# PCB-Relay-Board-V1.net
KiCad netlist of a schematic drawn in Altium Designer
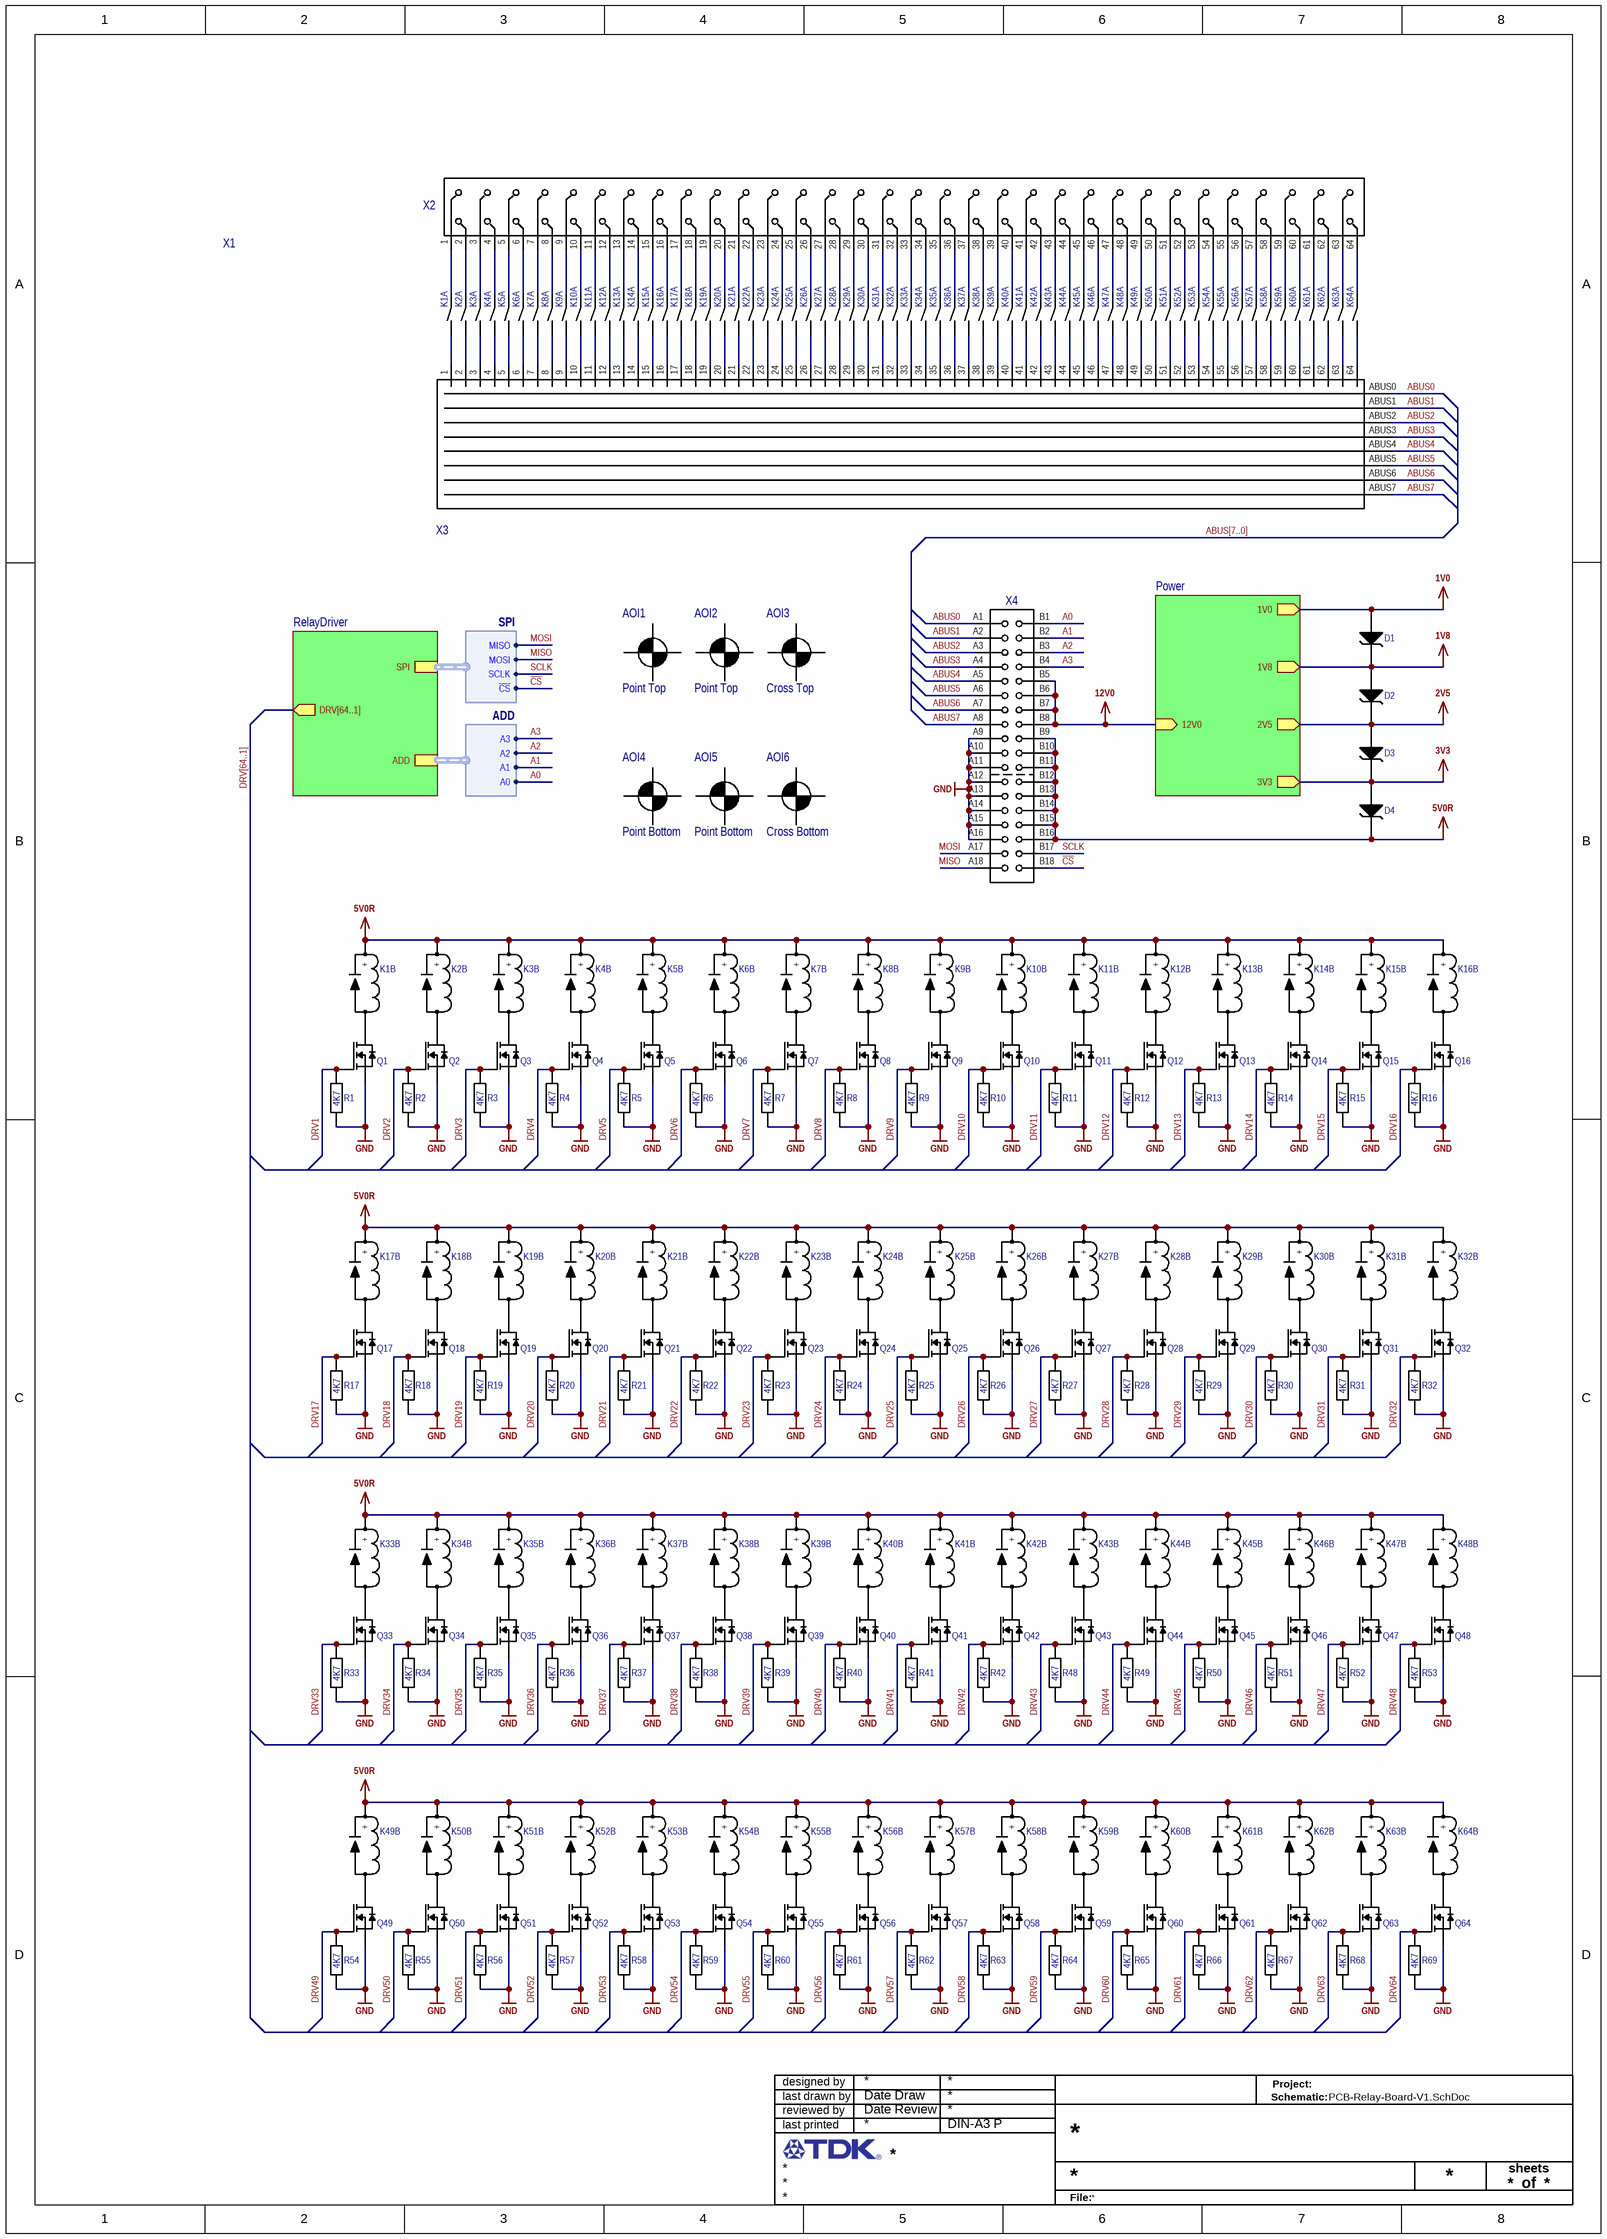
[diagram p0: PCB-Relay-Board-V1.SchDoc]

(export (version "E")
  (design (tool "Eeschema 10.0.6"))
  (components
    (comp (ref "AOI1")
      (value "AOI")
      (footprint "Fiducial Point")
      (description "Assembly AOI")
      (fields (field (name "SHAPE") "Point Top") (field (name "13. CREATED DATE/NAME") "AUG2018/Hören"))
      (libsource (lib "chickenfood") (part "Fiducial"))
    )
    (comp (ref "AOI2")
      (value "AOI")
      (footprint "Fiducial Point")
      (description "Assembly AOI")
      (fields (field (name "SHAPE") "Point Top") (field (name "13. CREATED DATE/NAME") "AUG2018/Hören"))
      (libsource (lib "chickenfood") (part "Fiducial"))
    )
    (comp (ref "AOI3")
      (value "AOI")
      (footprint "Fiducial Cross")
      (description "Assembly AOI")
      (fields (field (name "SHAPE") "Cross Top") (field (name "13. CREATED DATE/NAME") "AUG2018/Hören"))
      (libsource (lib "chickenfood") (part "Fiducial"))
    )
    (comp (ref "AOI4")
      (value "AOI")
      (footprint "Fiducial Point")
      (description "Assembly AOI")
      (fields (field (name "SHAPE") "Point Bottom") (field (name "13. CREATED DATE/NAME") "AUG2018/Hören"))
      (libsource (lib "chickenfood") (part "Fiducial"))
    )
    (comp (ref "AOI5")
      (value "AOI")
      (footprint "Fiducial Point")
      (description "Assembly AOI")
      (fields (field (name "SHAPE") "Point Bottom") (field (name "13. CREATED DATE/NAME") "AUG2018/Hören"))
      (libsource (lib "chickenfood") (part "Fiducial"))
    )
    (comp (ref "AOI6")
      (value "AOI")
      (footprint "Fiducial Cross")
      (description "Assembly AOI")
      (fields (field (name "SHAPE") "Cross Bottom") (field (name "13. CREATED DATE/NAME") "AUG2018/Hören"))
      (libsource (lib "chickenfood") (part "Fiducial"))
    )
    (comp (ref "D1")
      (value "D")
      (footprint "SOD128")
      (description "DIODE SCHOTTKY 40V 5A SOD128")
      (fields
        (field (name "02. DISTRIBUTOR PART NUMBER") "1727-5842-6-ND")
        (field (name "07. MANUFACTURER  PART NUMBER") "PMEG4050EP,115")
        (field (name "13. CREATED DATE/NAME") "AUG2018/Hören")
      )
      (libsource (lib "chickenfood") (part "Dz"))
    )
    (comp (ref "D2")
      (value "D")
      (footprint "SOD128")
      (description "DIODE SCHOTTKY 40V 5A SOD128")
      (fields
        (field (name "02. DISTRIBUTOR PART NUMBER") "1727-5842-6-ND")
        (field (name "07. MANUFACTURER  PART NUMBER") "PMEG4050EP,115")
        (field (name "13. CREATED DATE/NAME") "AUG2018/Hören")
      )
      (libsource (lib "chickenfood") (part "Dz"))
    )
    (comp (ref "D3")
      (value "D")
      (footprint "SOD128")
      (description "DIODE SCHOTTKY 40V 5A SOD128")
      (fields
        (field (name "02. DISTRIBUTOR PART NUMBER") "1727-5842-6-ND")
        (field (name "07. MANUFACTURER  PART NUMBER") "PMEG4050EP,115")
        (field (name "13. CREATED DATE/NAME") "AUG2018/Hören")
      )
      (libsource (lib "chickenfood") (part "Dz"))
    )
    (comp (ref "D4")
      (value "D")
      (footprint "SOD128")
      (description "DIODE SCHOTTKY 40V 5A SOD128")
      (fields
        (field (name "02. DISTRIBUTOR PART NUMBER") "1727-5842-6-ND")
        (field (name "07. MANUFACTURER  PART NUMBER") "PMEG4050EP,115")
        (field (name "13. CREATED DATE/NAME") "AUG2018/Hören")
      )
      (libsource (lib "chickenfood") (part "Dz"))
    )
    (comp (ref "K1")
      (value "K")
      (footprint "118-1A")
      (description "5V Signal Relais, Normal Open")
      (fields
        (field (name "02. DISTRIBUTOR PART NUMBER") "118-1-A-5/2D")
        (field (name "13. CREATED DATE/NAME") "20.12.17 S. Kaiser")
      )
      (libsource (lib "chickenfood") (part "118-1-A-5/2D"))
    )
    (comp (ref "K2")
      (value "K")
      (footprint "118-1A")
      (description "5V Signal Relais, Normal Open")
      (fields
        (field (name "02. DISTRIBUTOR PART NUMBER") "118-1-A-5/2D")
        (field (name "13. CREATED DATE/NAME") "20.12.17 S. Kaiser")
      )
      (libsource (lib "") (part "118-1-A-5/2D_1"))
    )
    (comp (ref "K3")
      (value "K")
      (footprint "118-1A")
      (description "5V Signal Relais, Normal Open")
      (fields
        (field (name "02. DISTRIBUTOR PART NUMBER") "118-1-A-5/2D")
        (field (name "13. CREATED DATE/NAME") "20.12.17 S. Kaiser")
      )
      (libsource (lib "chickenfood") (part "118-1-A-5/2D"))
    )
    (comp (ref "K4")
      (value "K")
      (footprint "118-1A")
      (description "5V Signal Relais, Normal Open")
      (fields
        (field (name "02. DISTRIBUTOR PART NUMBER") "118-1-A-5/2D")
        (field (name "13. CREATED DATE/NAME") "20.12.17 S. Kaiser")
      )
      (libsource (lib "chickenfood") (part "118-1-A-5/2D"))
    )
    (comp (ref "K5")
      (value "K")
      (footprint "118-1A")
      (description "5V Signal Relais, Normal Open")
      (fields
        (field (name "02. DISTRIBUTOR PART NUMBER") "118-1-A-5/2D")
        (field (name "13. CREATED DATE/NAME") "20.12.17 S. Kaiser")
      )
      (libsource (lib "") (part "118-1-A-5/2D_1"))
    )
    (comp (ref "K6")
      (value "K")
      (footprint "118-1A")
      (description "5V Signal Relais, Normal Open")
      (fields
        (field (name "02. DISTRIBUTOR PART NUMBER") "118-1-A-5/2D")
        (field (name "13. CREATED DATE/NAME") "20.12.17 S. Kaiser")
      )
      (libsource (lib "") (part "118-1-A-5/2D_1"))
    )
    (comp (ref "K7")
      (value "K")
      (footprint "118-1A")
      (description "5V Signal Relais, Normal Open")
      (fields
        (field (name "02. DISTRIBUTOR PART NUMBER") "118-1-A-5/2D")
        (field (name "13. CREATED DATE/NAME") "20.12.17 S. Kaiser")
      )
      (libsource (lib "chickenfood") (part "118-1-A-5/2D"))
    )
    (comp (ref "K8")
      (value "K")
      (footprint "118-1A")
      (description "5V Signal Relais, Normal Open")
      (fields
        (field (name "02. DISTRIBUTOR PART NUMBER") "118-1-A-5/2D")
        (field (name "13. CREATED DATE/NAME") "20.12.17 S. Kaiser")
      )
      (libsource (lib "chickenfood") (part "118-1-A-5/2D"))
    )
    (comp (ref "K9")
      (value "K")
      (footprint "118-1A")
      (description "5V Signal Relais, Normal Open")
      (fields
        (field (name "02. DISTRIBUTOR PART NUMBER") "118-1-A-5/2D")
        (field (name "13. CREATED DATE/NAME") "20.12.17 S. Kaiser")
      )
      (libsource (lib "") (part "118-1-A-5/2D_1"))
    )
    (comp (ref "K10")
      (value "K")
      (footprint "118-1A")
      (description "5V Signal Relais, Normal Open")
      (fields
        (field (name "02. DISTRIBUTOR PART NUMBER") "118-1-A-5/2D")
        (field (name "13. CREATED DATE/NAME") "20.12.17 S. Kaiser")
      )
      (libsource (lib "") (part "118-1-A-5/2D_1"))
    )
    (comp (ref "K11")
      (value "K")
      (footprint "118-1A")
      (description "5V Signal Relais, Normal Open")
      (fields
        (field (name "02. DISTRIBUTOR PART NUMBER") "118-1-A-5/2D")
        (field (name "13. CREATED DATE/NAME") "20.12.17 S. Kaiser")
      )
      (libsource (lib "") (part "118-1-A-5/2D_1"))
    )
    (comp (ref "K12")
      (value "K")
      (footprint "118-1A")
      (description "5V Signal Relais, Normal Open")
      (fields
        (field (name "02. DISTRIBUTOR PART NUMBER") "118-1-A-5/2D")
        (field (name "13. CREATED DATE/NAME") "20.12.17 S. Kaiser")
      )
      (libsource (lib "chickenfood") (part "118-1-A-5/2D"))
    )
    (comp (ref "K13")
      (value "K")
      (footprint "118-1A")
      (description "5V Signal Relais, Normal Open")
      (fields
        (field (name "02. DISTRIBUTOR PART NUMBER") "118-1-A-5/2D")
        (field (name "13. CREATED DATE/NAME") "20.12.17 S. Kaiser")
      )
      (libsource (lib "") (part "118-1-A-5/2D_1"))
    )
    (comp (ref "K14")
      (value "K")
      (footprint "118-1A")
      (description "5V Signal Relais, Normal Open")
      (fields
        (field (name "02. DISTRIBUTOR PART NUMBER") "118-1-A-5/2D")
        (field (name "13. CREATED DATE/NAME") "20.12.17 S. Kaiser")
      )
      (libsource (lib "chickenfood") (part "118-1-A-5/2D"))
    )
    (comp (ref "K15")
      (value "K")
      (footprint "118-1A")
      (description "5V Signal Relais, Normal Open")
      (fields
        (field (name "02. DISTRIBUTOR PART NUMBER") "118-1-A-5/2D")
        (field (name "13. CREATED DATE/NAME") "20.12.17 S. Kaiser")
      )
      (libsource (lib "chickenfood") (part "118-1-A-5/2D"))
    )
    (comp (ref "K16")
      (value "K")
      (footprint "118-1A")
      (description "5V Signal Relais, Normal Open")
      (fields
        (field (name "02. DISTRIBUTOR PART NUMBER") "118-1-A-5/2D")
        (field (name "13. CREATED DATE/NAME") "20.12.17 S. Kaiser")
      )
      (libsource (lib "chickenfood") (part "118-1-A-5/2D"))
    )
    (comp (ref "K17")
      (value "K")
      (footprint "118-1A")
      (description "5V Signal Relais, Normal Open")
      (fields
        (field (name "02. DISTRIBUTOR PART NUMBER") "118-1-A-5/2D")
        (field (name "13. CREATED DATE/NAME") "20.12.17 S. Kaiser")
      )
      (libsource (lib "") (part "118-1-A-5/2D_1"))
    )
    (comp (ref "K18")
      (value "K")
      (footprint "118-1A")
      (description "5V Signal Relais, Normal Open")
      (fields
        (field (name "02. DISTRIBUTOR PART NUMBER") "118-1-A-5/2D")
        (field (name "13. CREATED DATE/NAME") "20.12.17 S. Kaiser")
      )
      (libsource (lib "chickenfood") (part "118-1-A-5/2D"))
    )
    (comp (ref "K19")
      (value "K")
      (footprint "118-1A")
      (description "5V Signal Relais, Normal Open")
      (fields
        (field (name "02. DISTRIBUTOR PART NUMBER") "118-1-A-5/2D")
        (field (name "13. CREATED DATE/NAME") "20.12.17 S. Kaiser")
      )
      (libsource (lib "chickenfood") (part "118-1-A-5/2D"))
    )
    (comp (ref "K20")
      (value "K")
      (footprint "118-1A")
      (description "5V Signal Relais, Normal Open")
      (fields
        (field (name "02. DISTRIBUTOR PART NUMBER") "118-1-A-5/2D")
        (field (name "13. CREATED DATE/NAME") "20.12.17 S. Kaiser")
      )
      (libsource (lib "chickenfood") (part "118-1-A-5/2D"))
    )
    (comp (ref "K21")
      (value "K")
      (footprint "118-1A")
      (description "5V Signal Relais, Normal Open")
      (fields
        (field (name "02. DISTRIBUTOR PART NUMBER") "118-1-A-5/2D")
        (field (name "13. CREATED DATE/NAME") "20.12.17 S. Kaiser")
      )
      (libsource (lib "") (part "118-1-A-5/2D_1"))
    )
    (comp (ref "K22")
      (value "K")
      (footprint "118-1A")
      (description "5V Signal Relais, Normal Open")
      (fields
        (field (name "02. DISTRIBUTOR PART NUMBER") "118-1-A-5/2D")
        (field (name "13. CREATED DATE/NAME") "20.12.17 S. Kaiser")
      )
      (libsource (lib "chickenfood") (part "118-1-A-5/2D"))
    )
    (comp (ref "K23")
      (value "K")
      (footprint "118-1A")
      (description "5V Signal Relais, Normal Open")
      (fields
        (field (name "02. DISTRIBUTOR PART NUMBER") "118-1-A-5/2D")
        (field (name "13. CREATED DATE/NAME") "20.12.17 S. Kaiser")
      )
      (libsource (lib "chickenfood") (part "118-1-A-5/2D"))
    )
    (comp (ref "K24")
      (value "K")
      (footprint "118-1A")
      (description "5V Signal Relais, Normal Open")
      (fields
        (field (name "02. DISTRIBUTOR PART NUMBER") "118-1-A-5/2D")
        (field (name "13. CREATED DATE/NAME") "20.12.17 S. Kaiser")
      )
      (libsource (lib "") (part "118-1-A-5/2D_1"))
    )
    (comp (ref "K25")
      (value "K")
      (footprint "118-1A")
      (description "5V Signal Relais, Normal Open")
      (fields
        (field (name "02. DISTRIBUTOR PART NUMBER") "118-1-A-5/2D")
        (field (name "13. CREATED DATE/NAME") "20.12.17 S. Kaiser")
      )
      (libsource (lib "") (part "118-1-A-5/2D_1"))
    )
    (comp (ref "K26")
      (value "K")
      (footprint "118-1A")
      (description "5V Signal Relais, Normal Open")
      (fields
        (field (name "02. DISTRIBUTOR PART NUMBER") "118-1-A-5/2D")
        (field (name "13. CREATED DATE/NAME") "20.12.17 S. Kaiser")
      )
      (libsource (lib "chickenfood") (part "118-1-A-5/2D"))
    )
    (comp (ref "K27")
      (value "K")
      (footprint "118-1A")
      (description "5V Signal Relais, Normal Open")
      (fields
        (field (name "02. DISTRIBUTOR PART NUMBER") "118-1-A-5/2D")
        (field (name "13. CREATED DATE/NAME") "20.12.17 S. Kaiser")
      )
      (libsource (lib "chickenfood") (part "118-1-A-5/2D"))
    )
    (comp (ref "K28")
      (value "K")
      (footprint "118-1A")
      (description "5V Signal Relais, Normal Open")
      (fields
        (field (name "02. DISTRIBUTOR PART NUMBER") "118-1-A-5/2D")
        (field (name "13. CREATED DATE/NAME") "20.12.17 S. Kaiser")
      )
      (libsource (lib "") (part "118-1-A-5/2D_1"))
    )
    (comp (ref "K29")
      (value "K")
      (footprint "118-1A")
      (description "5V Signal Relais, Normal Open")
      (fields
        (field (name "02. DISTRIBUTOR PART NUMBER") "118-1-A-5/2D")
        (field (name "13. CREATED DATE/NAME") "20.12.17 S. Kaiser")
      )
      (libsource (lib "chickenfood") (part "118-1-A-5/2D"))
    )
    (comp (ref "K30")
      (value "K")
      (footprint "118-1A")
      (description "5V Signal Relais, Normal Open")
      (fields
        (field (name "02. DISTRIBUTOR PART NUMBER") "118-1-A-5/2D")
        (field (name "13. CREATED DATE/NAME") "20.12.17 S. Kaiser")
      )
      (libsource (lib "") (part "118-1-A-5/2D_1"))
    )
    (comp (ref "K31")
      (value "K")
      (footprint "118-1A")
      (description "5V Signal Relais, Normal Open")
      (fields
        (field (name "02. DISTRIBUTOR PART NUMBER") "118-1-A-5/2D")
        (field (name "13. CREATED DATE/NAME") "20.12.17 S. Kaiser")
      )
      (libsource (lib "") (part "118-1-A-5/2D_1"))
    )
    (comp (ref "K32")
      (value "K")
      (footprint "118-1A")
      (description "5V Signal Relais, Normal Open")
      (fields
        (field (name "02. DISTRIBUTOR PART NUMBER") "118-1-A-5/2D")
        (field (name "13. CREATED DATE/NAME") "20.12.17 S. Kaiser")
      )
      (libsource (lib "chickenfood") (part "118-1-A-5/2D"))
    )
    (comp (ref "K33")
      (value "K")
      (footprint "118-1A")
      (description "5V Signal Relais, Normal Open")
      (fields
        (field (name "02. DISTRIBUTOR PART NUMBER") "118-1-A-5/2D")
        (field (name "13. CREATED DATE/NAME") "20.12.17 S. Kaiser")
      )
      (libsource (lib "") (part "118-1-A-5/2D_1"))
    )
    (comp (ref "K34")
      (value "K")
      (footprint "118-1A")
      (description "5V Signal Relais, Normal Open")
      (fields
        (field (name "02. DISTRIBUTOR PART NUMBER") "118-1-A-5/2D")
        (field (name "13. CREATED DATE/NAME") "20.12.17 S. Kaiser")
      )
      (libsource (lib "") (part "118-1-A-5/2D_1"))
    )
    (comp (ref "K35")
      (value "K")
      (footprint "118-1A")
      (description "5V Signal Relais, Normal Open")
      (fields
        (field (name "02. DISTRIBUTOR PART NUMBER") "118-1-A-5/2D")
        (field (name "13. CREATED DATE/NAME") "20.12.17 S. Kaiser")
      )
      (libsource (lib "chickenfood") (part "118-1-A-5/2D"))
    )
    (comp (ref "K36")
      (value "K")
      (footprint "118-1A")
      (description "5V Signal Relais, Normal Open")
      (fields
        (field (name "02. DISTRIBUTOR PART NUMBER") "118-1-A-5/2D")
        (field (name "13. CREATED DATE/NAME") "20.12.17 S. Kaiser")
      )
      (libsource (lib "chickenfood") (part "118-1-A-5/2D"))
    )
    (comp (ref "K37")
      (value "K")
      (footprint "118-1A")
      (description "5V Signal Relais, Normal Open")
      (fields
        (field (name "02. DISTRIBUTOR PART NUMBER") "118-1-A-5/2D")
        (field (name "13. CREATED DATE/NAME") "20.12.17 S. Kaiser")
      )
      (libsource (lib "chickenfood") (part "118-1-A-5/2D"))
    )
    (comp (ref "K38")
      (value "K")
      (footprint "118-1A")
      (description "5V Signal Relais, Normal Open")
      (fields
        (field (name "02. DISTRIBUTOR PART NUMBER") "118-1-A-5/2D")
        (field (name "13. CREATED DATE/NAME") "20.12.17 S. Kaiser")
      )
      (libsource (lib "") (part "118-1-A-5/2D_1"))
    )
    (comp (ref "K39")
      (value "K")
      (footprint "118-1A")
      (description "5V Signal Relais, Normal Open")
      (fields
        (field (name "02. DISTRIBUTOR PART NUMBER") "118-1-A-5/2D")
        (field (name "13. CREATED DATE/NAME") "20.12.17 S. Kaiser")
      )
      (libsource (lib "chickenfood") (part "118-1-A-5/2D"))
    )
    (comp (ref "K40")
      (value "K")
      (footprint "118-1A")
      (description "5V Signal Relais, Normal Open")
      (fields
        (field (name "02. DISTRIBUTOR PART NUMBER") "118-1-A-5/2D")
        (field (name "13. CREATED DATE/NAME") "20.12.17 S. Kaiser")
      )
      (libsource (lib "chickenfood") (part "118-1-A-5/2D"))
    )
    (comp (ref "K41")
      (value "K")
      (footprint "118-1A")
      (description "5V Signal Relais, Normal Open")
      (fields
        (field (name "02. DISTRIBUTOR PART NUMBER") "118-1-A-5/2D")
        (field (name "13. CREATED DATE/NAME") "20.12.17 S. Kaiser")
      )
      (libsource (lib "chickenfood") (part "118-1-A-5/2D"))
    )
    (comp (ref "K42")
      (value "K")
      (footprint "118-1A")
      (description "5V Signal Relais, Normal Open")
      (fields
        (field (name "02. DISTRIBUTOR PART NUMBER") "118-1-A-5/2D")
        (field (name "13. CREATED DATE/NAME") "20.12.17 S. Kaiser")
      )
      (libsource (lib "") (part "118-1-A-5/2D_1"))
    )
    (comp (ref "K43")
      (value "K")
      (footprint "118-1A")
      (description "5V Signal Relais, Normal Open")
      (fields
        (field (name "02. DISTRIBUTOR PART NUMBER") "118-1-A-5/2D")
        (field (name "13. CREATED DATE/NAME") "20.12.17 S. Kaiser")
      )
      (libsource (lib "chickenfood") (part "118-1-A-5/2D"))
    )
    (comp (ref "K44")
      (value "K")
      (footprint "118-1A")
      (description "5V Signal Relais, Normal Open")
      (fields
        (field (name "02. DISTRIBUTOR PART NUMBER") "118-1-A-5/2D")
        (field (name "13. CREATED DATE/NAME") "20.12.17 S. Kaiser")
      )
      (libsource (lib "") (part "118-1-A-5/2D_1"))
    )
    (comp (ref "K45")
      (value "K")
      (footprint "118-1A")
      (description "5V Signal Relais, Normal Open")
      (fields
        (field (name "02. DISTRIBUTOR PART NUMBER") "118-1-A-5/2D")
        (field (name "13. CREATED DATE/NAME") "20.12.17 S. Kaiser")
      )
      (libsource (lib "chickenfood") (part "118-1-A-5/2D"))
    )
    (comp (ref "K46")
      (value "K")
      (footprint "118-1A")
      (description "5V Signal Relais, Normal Open")
      (fields
        (field (name "02. DISTRIBUTOR PART NUMBER") "118-1-A-5/2D")
        (field (name "13. CREATED DATE/NAME") "20.12.17 S. Kaiser")
      )
      (libsource (lib "") (part "118-1-A-5/2D_1"))
    )
    (comp (ref "K47")
      (value "K")
      (footprint "118-1A")
      (description "5V Signal Relais, Normal Open")
      (fields
        (field (name "02. DISTRIBUTOR PART NUMBER") "118-1-A-5/2D")
        (field (name "13. CREATED DATE/NAME") "20.12.17 S. Kaiser")
      )
      (libsource (lib "chickenfood") (part "118-1-A-5/2D"))
    )
    (comp (ref "K48")
      (value "K")
      (footprint "118-1A")
      (description "5V Signal Relais, Normal Open")
      (fields
        (field (name "02. DISTRIBUTOR PART NUMBER") "118-1-A-5/2D")
        (field (name "13. CREATED DATE/NAME") "20.12.17 S. Kaiser")
      )
      (libsource (lib "chickenfood") (part "118-1-A-5/2D"))
    )
    (comp (ref "K49")
      (value "K")
      (footprint "118-1A")
      (description "5V Signal Relais, Normal Open")
      (fields
        (field (name "02. DISTRIBUTOR PART NUMBER") "118-1-A-5/2D")
        (field (name "13. CREATED DATE/NAME") "20.12.17 S. Kaiser")
      )
      (libsource (lib "") (part "118-1-A-5/2D_1"))
    )
    (comp (ref "K50")
      (value "K")
      (footprint "118-1A")
      (description "5V Signal Relais, Normal Open")
      (fields
        (field (name "02. DISTRIBUTOR PART NUMBER") "118-1-A-5/2D")
        (field (name "13. CREATED DATE/NAME") "20.12.17 S. Kaiser")
      )
      (libsource (lib "chickenfood") (part "118-1-A-5/2D"))
    )
    (comp (ref "K51")
      (value "K")
      (footprint "118-1A")
      (description "5V Signal Relais, Normal Open")
      (fields
        (field (name "02. DISTRIBUTOR PART NUMBER") "118-1-A-5/2D")
        (field (name "13. CREATED DATE/NAME") "20.12.17 S. Kaiser")
      )
      (libsource (lib "") (part "118-1-A-5/2D_1"))
    )
    (comp (ref "K52")
      (value "K")
      (footprint "118-1A")
      (description "5V Signal Relais, Normal Open")
      (fields
        (field (name "02. DISTRIBUTOR PART NUMBER") "118-1-A-5/2D")
        (field (name "13. CREATED DATE/NAME") "20.12.17 S. Kaiser")
      )
      (libsource (lib "chickenfood") (part "118-1-A-5/2D"))
    )
    (comp (ref "K53")
      (value "K")
      (footprint "118-1A")
      (description "5V Signal Relais, Normal Open")
      (fields
        (field (name "02. DISTRIBUTOR PART NUMBER") "118-1-A-5/2D")
        (field (name "13. CREATED DATE/NAME") "20.12.17 S. Kaiser")
      )
      (libsource (lib "chickenfood") (part "118-1-A-5/2D"))
    )
    (comp (ref "K54")
      (value "K")
      (footprint "118-1A")
      (description "5V Signal Relais, Normal Open")
      (fields
        (field (name "02. DISTRIBUTOR PART NUMBER") "118-1-A-5/2D")
        (field (name "13. CREATED DATE/NAME") "20.12.17 S. Kaiser")
      )
      (libsource (lib "chickenfood") (part "118-1-A-5/2D"))
    )
    (comp (ref "K55")
      (value "K")
      (footprint "118-1A")
      (description "5V Signal Relais, Normal Open")
      (fields
        (field (name "02. DISTRIBUTOR PART NUMBER") "118-1-A-5/2D")
        (field (name "13. CREATED DATE/NAME") "20.12.17 S. Kaiser")
      )
      (libsource (lib "") (part "118-1-A-5/2D_1"))
    )
    (comp (ref "K56")
      (value "K")
      (footprint "118-1A")
      (description "5V Signal Relais, Normal Open")
      (fields
        (field (name "02. DISTRIBUTOR PART NUMBER") "118-1-A-5/2D")
        (field (name "13. CREATED DATE/NAME") "20.12.17 S. Kaiser")
      )
      (libsource (lib "") (part "118-1-A-5/2D_1"))
    )
    (comp (ref "K57")
      (value "K")
      (footprint "118-1A")
      (description "5V Signal Relais, Normal Open")
      (fields
        (field (name "02. DISTRIBUTOR PART NUMBER") "118-1-A-5/2D")
        (field (name "13. CREATED DATE/NAME") "20.12.17 S. Kaiser")
      )
      (libsource (lib "chickenfood") (part "118-1-A-5/2D"))
    )
    (comp (ref "K58")
      (value "K")
      (footprint "118-1A")
      (description "5V Signal Relais, Normal Open")
      (fields
        (field (name "02. DISTRIBUTOR PART NUMBER") "118-1-A-5/2D")
        (field (name "13. CREATED DATE/NAME") "20.12.17 S. Kaiser")
      )
      (libsource (lib "") (part "118-1-A-5/2D_1"))
    )
    (comp (ref "K59")
      (value "K")
      (footprint "118-1A")
      (description "5V Signal Relais, Normal Open")
      (fields
        (field (name "02. DISTRIBUTOR PART NUMBER") "118-1-A-5/2D")
        (field (name "13. CREATED DATE/NAME") "20.12.17 S. Kaiser")
      )
      (libsource (lib "chickenfood") (part "118-1-A-5/2D"))
    )
    (comp (ref "K60")
      (value "K")
      (footprint "118-1A")
      (description "5V Signal Relais, Normal Open")
      (fields
        (field (name "02. DISTRIBUTOR PART NUMBER") "118-1-A-5/2D")
        (field (name "13. CREATED DATE/NAME") "20.12.17 S. Kaiser")
      )
      (libsource (lib "") (part "118-1-A-5/2D_1"))
    )
    (comp (ref "K61")
      (value "K")
      (footprint "118-1A")
      (description "5V Signal Relais, Normal Open")
      (fields
        (field (name "02. DISTRIBUTOR PART NUMBER") "118-1-A-5/2D")
        (field (name "13. CREATED DATE/NAME") "20.12.17 S. Kaiser")
      )
      (libsource (lib "") (part "118-1-A-5/2D_1"))
    )
    (comp (ref "K62")
      (value "K")
      (footprint "118-1A")
      (description "5V Signal Relais, Normal Open")
      (fields
        (field (name "02. DISTRIBUTOR PART NUMBER") "118-1-A-5/2D")
        (field (name "13. CREATED DATE/NAME") "20.12.17 S. Kaiser")
      )
      (libsource (lib "chickenfood") (part "118-1-A-5/2D"))
    )
    (comp (ref "K63")
      (value "K")
      (footprint "118-1A")
      (description "5V Signal Relais, Normal Open")
      (fields
        (field (name "02. DISTRIBUTOR PART NUMBER") "118-1-A-5/2D")
        (field (name "13. CREATED DATE/NAME") "20.12.17 S. Kaiser")
      )
      (libsource (lib "") (part "118-1-A-5/2D_1"))
    )
    (comp (ref "K64")
      (value "K")
      (footprint "118-1A")
      (description "5V Signal Relais, Normal Open")
      (fields
        (field (name "02. DISTRIBUTOR PART NUMBER") "118-1-A-5/2D")
        (field (name "13. CREATED DATE/NAME") "20.12.17 S. Kaiser")
      )
      (libsource (lib "") (part "118-1-A-5/2D_1"))
    )
    (comp (ref "Q1")
      (value "Q")
      (footprint "SOT23-3")
      (description "MOSFET N-CH 25V 680MA SOT-23")
      (fields
        (field (name "02. DISTRIBUTOR PART NUMBER") "FDV303NDKR-ND")
        (field (name "07. MANUFACTURER  PART NUMBER") "FDV303N")
        (field (name "13. CREATED DATE/NAME") "AUG 2018 / Hören")
      )
      (libsource (lib "SCT8-Board1") (part "FDV303N"))
    )
    (comp (ref "Q2")
      (value "Q")
      (footprint "SOT23-3")
      (description "MOSFET N-CH 25V 680MA SOT-23")
      (fields
        (field (name "02. DISTRIBUTOR PART NUMBER") "FDV303NDKR-ND")
        (field (name "07. MANUFACTURER  PART NUMBER") "FDV303N")
        (field (name "13. CREATED DATE/NAME") "AUG 2018 / Hören")
      )
      (libsource (lib "SCT8-Board1") (part "FDV303N"))
    )
    (comp (ref "Q3")
      (value "Q")
      (footprint "SOT23-3")
      (description "MOSFET N-CH 25V 680MA SOT-23")
      (fields
        (field (name "02. DISTRIBUTOR PART NUMBER") "FDV303NDKR-ND")
        (field (name "07. MANUFACTURER  PART NUMBER") "FDV303N")
        (field (name "13. CREATED DATE/NAME") "AUG 2018 / Hören")
      )
      (libsource (lib "SCT8-Board1") (part "FDV303N"))
    )
    (comp (ref "Q4")
      (value "Q")
      (footprint "SOT23-3")
      (description "MOSFET N-CH 25V 680MA SOT-23")
      (fields
        (field (name "02. DISTRIBUTOR PART NUMBER") "FDV303NDKR-ND")
        (field (name "07. MANUFACTURER  PART NUMBER") "FDV303N")
        (field (name "13. CREATED DATE/NAME") "AUG 2018 / Hören")
      )
      (libsource (lib "SCT8-Board1") (part "FDV303N"))
    )
    (comp (ref "Q5")
      (value "Q")
      (footprint "SOT23-3")
      (description "MOSFET N-CH 25V 680MA SOT-23")
      (fields
        (field (name "02. DISTRIBUTOR PART NUMBER") "FDV303NDKR-ND")
        (field (name "07. MANUFACTURER  PART NUMBER") "FDV303N")
        (field (name "13. CREATED DATE/NAME") "AUG 2018 / Hören")
      )
      (libsource (lib "SCT8-Board1") (part "FDV303N"))
    )
    (comp (ref "Q6")
      (value "Q")
      (footprint "SOT23-3")
      (description "MOSFET N-CH 25V 680MA SOT-23")
      (fields
        (field (name "02. DISTRIBUTOR PART NUMBER") "FDV303NDKR-ND")
        (field (name "07. MANUFACTURER  PART NUMBER") "FDV303N")
        (field (name "13. CREATED DATE/NAME") "AUG 2018 / Hören")
      )
      (libsource (lib "SCT8-Board1") (part "FDV303N"))
    )
    (comp (ref "Q7")
      (value "Q")
      (footprint "SOT23-3")
      (description "MOSFET N-CH 25V 680MA SOT-23")
      (fields
        (field (name "02. DISTRIBUTOR PART NUMBER") "FDV303NDKR-ND")
        (field (name "07. MANUFACTURER  PART NUMBER") "FDV303N")
        (field (name "13. CREATED DATE/NAME") "AUG 2018 / Hören")
      )
      (libsource (lib "SCT8-Board1") (part "FDV303N"))
    )
    (comp (ref "Q8")
      (value "Q")
      (footprint "SOT23-3")
      (description "MOSFET N-CH 25V 680MA SOT-23")
      (fields
        (field (name "02. DISTRIBUTOR PART NUMBER") "FDV303NDKR-ND")
        (field (name "07. MANUFACTURER  PART NUMBER") "FDV303N")
        (field (name "13. CREATED DATE/NAME") "AUG 2018 / Hören")
      )
      (libsource (lib "SCT8-Board1") (part "FDV303N"))
    )
    (comp (ref "Q9")
      (value "Q")
      (footprint "SOT23-3")
      (description "MOSFET N-CH 25V 680MA SOT-23")
      (fields
        (field (name "02. DISTRIBUTOR PART NUMBER") "FDV303NDKR-ND")
        (field (name "07. MANUFACTURER  PART NUMBER") "FDV303N")
        (field (name "13. CREATED DATE/NAME") "AUG 2018 / Hören")
      )
      (libsource (lib "SCT8-Board1") (part "FDV303N"))
    )
    (comp (ref "Q10")
      (value "Q")
      (footprint "SOT23-3")
      (description "MOSFET N-CH 25V 680MA SOT-23")
      (fields
        (field (name "02. DISTRIBUTOR PART NUMBER") "FDV303NDKR-ND")
        (field (name "07. MANUFACTURER  PART NUMBER") "FDV303N")
        (field (name "13. CREATED DATE/NAME") "AUG 2018 / Hören")
      )
      (libsource (lib "SCT8-Board1") (part "FDV303N"))
    )
    (comp (ref "Q11")
      (value "Q")
      (footprint "SOT23-3")
      (description "MOSFET N-CH 25V 680MA SOT-23")
      (fields
        (field (name "02. DISTRIBUTOR PART NUMBER") "FDV303NDKR-ND")
        (field (name "07. MANUFACTURER  PART NUMBER") "FDV303N")
        (field (name "13. CREATED DATE/NAME") "AUG 2018 / Hören")
      )
      (libsource (lib "SCT8-Board1") (part "FDV303N"))
    )
    (comp (ref "Q12")
      (value "Q")
      (footprint "SOT23-3")
      (description "MOSFET N-CH 25V 680MA SOT-23")
      (fields
        (field (name "02. DISTRIBUTOR PART NUMBER") "FDV303NDKR-ND")
        (field (name "07. MANUFACTURER  PART NUMBER") "FDV303N")
        (field (name "13. CREATED DATE/NAME") "AUG 2018 / Hören")
      )
      (libsource (lib "SCT8-Board1") (part "FDV303N"))
    )
    (comp (ref "Q13")
      (value "Q")
      (footprint "SOT23-3")
      (description "MOSFET N-CH 25V 680MA SOT-23")
      (fields
        (field (name "02. DISTRIBUTOR PART NUMBER") "FDV303NDKR-ND")
        (field (name "07. MANUFACTURER  PART NUMBER") "FDV303N")
        (field (name "13. CREATED DATE/NAME") "AUG 2018 / Hören")
      )
      (libsource (lib "SCT8-Board1") (part "FDV303N"))
    )
    (comp (ref "Q14")
      (value "Q")
      (footprint "SOT23-3")
      (description "MOSFET N-CH 25V 680MA SOT-23")
      (fields
        (field (name "02. DISTRIBUTOR PART NUMBER") "FDV303NDKR-ND")
        (field (name "07. MANUFACTURER  PART NUMBER") "FDV303N")
        (field (name "13. CREATED DATE/NAME") "AUG 2018 / Hören")
      )
      (libsource (lib "SCT8-Board1") (part "FDV303N"))
    )
    (comp (ref "Q15")
      (value "Q")
      (footprint "SOT23-3")
      (description "MOSFET N-CH 25V 680MA SOT-23")
      (fields
        (field (name "02. DISTRIBUTOR PART NUMBER") "FDV303NDKR-ND")
        (field (name "07. MANUFACTURER  PART NUMBER") "FDV303N")
        (field (name "13. CREATED DATE/NAME") "AUG 2018 / Hören")
      )
      (libsource (lib "SCT8-Board1") (part "FDV303N"))
    )
    (comp (ref "Q16")
      (value "Q")
      (footprint "SOT23-3")
      (description "MOSFET N-CH 25V 680MA SOT-23")
      (fields
        (field (name "02. DISTRIBUTOR PART NUMBER") "FDV303NDKR-ND")
        (field (name "07. MANUFACTURER  PART NUMBER") "FDV303N")
        (field (name "13. CREATED DATE/NAME") "AUG 2018 / Hören")
      )
      (libsource (lib "SCT8-Board1") (part "FDV303N"))
    )
    (comp (ref "Q17")
      (value "Q")
      (footprint "SOT23-3")
      (description "MOSFET N-CH 25V 680MA SOT-23")
      (fields
        (field (name "02. DISTRIBUTOR PART NUMBER") "FDV303NDKR-ND")
        (field (name "07. MANUFACTURER  PART NUMBER") "FDV303N")
        (field (name "13. CREATED DATE/NAME") "AUG 2018 / Hören")
      )
      (libsource (lib "SCT8-Board1") (part "FDV303N"))
    )
    (comp (ref "Q18")
      (value "Q")
      (footprint "SOT23-3")
      (description "MOSFET N-CH 25V 680MA SOT-23")
      (fields
        (field (name "02. DISTRIBUTOR PART NUMBER") "FDV303NDKR-ND")
        (field (name "07. MANUFACTURER  PART NUMBER") "FDV303N")
        (field (name "13. CREATED DATE/NAME") "AUG 2018 / Hören")
      )
      (libsource (lib "SCT8-Board1") (part "FDV303N"))
    )
    (comp (ref "Q19")
      (value "Q")
      (footprint "SOT23-3")
      (description "MOSFET N-CH 25V 680MA SOT-23")
      (fields
        (field (name "02. DISTRIBUTOR PART NUMBER") "FDV303NDKR-ND")
        (field (name "07. MANUFACTURER  PART NUMBER") "FDV303N")
        (field (name "13. CREATED DATE/NAME") "AUG 2018 / Hören")
      )
      (libsource (lib "SCT8-Board1") (part "FDV303N"))
    )
    (comp (ref "Q20")
      (value "Q")
      (footprint "SOT23-3")
      (description "MOSFET N-CH 25V 680MA SOT-23")
      (fields
        (field (name "02. DISTRIBUTOR PART NUMBER") "FDV303NDKR-ND")
        (field (name "07. MANUFACTURER  PART NUMBER") "FDV303N")
        (field (name "13. CREATED DATE/NAME") "AUG 2018 / Hören")
      )
      (libsource (lib "SCT8-Board1") (part "FDV303N"))
    )
    (comp (ref "Q21")
      (value "Q")
      (footprint "SOT23-3")
      (description "MOSFET N-CH 25V 680MA SOT-23")
      (fields
        (field (name "02. DISTRIBUTOR PART NUMBER") "FDV303NDKR-ND")
        (field (name "07. MANUFACTURER  PART NUMBER") "FDV303N")
        (field (name "13. CREATED DATE/NAME") "AUG 2018 / Hören")
      )
      (libsource (lib "SCT8-Board1") (part "FDV303N"))
    )
    (comp (ref "Q22")
      (value "Q")
      (footprint "SOT23-3")
      (description "MOSFET N-CH 25V 680MA SOT-23")
      (fields
        (field (name "02. DISTRIBUTOR PART NUMBER") "FDV303NDKR-ND")
        (field (name "07. MANUFACTURER  PART NUMBER") "FDV303N")
        (field (name "13. CREATED DATE/NAME") "AUG 2018 / Hören")
      )
      (libsource (lib "SCT8-Board1") (part "FDV303N"))
    )
    (comp (ref "Q23")
      (value "Q")
      (footprint "SOT23-3")
      (description "MOSFET N-CH 25V 680MA SOT-23")
      (fields
        (field (name "02. DISTRIBUTOR PART NUMBER") "FDV303NDKR-ND")
        (field (name "07. MANUFACTURER  PART NUMBER") "FDV303N")
        (field (name "13. CREATED DATE/NAME") "AUG 2018 / Hören")
      )
      (libsource (lib "SCT8-Board1") (part "FDV303N"))
    )
    (comp (ref "Q24")
      (value "Q")
      (footprint "SOT23-3")
      (description "MOSFET N-CH 25V 680MA SOT-23")
      (fields
        (field (name "02. DISTRIBUTOR PART NUMBER") "FDV303NDKR-ND")
        (field (name "07. MANUFACTURER  PART NUMBER") "FDV303N")
        (field (name "13. CREATED DATE/NAME") "AUG 2018 / Hören")
      )
      (libsource (lib "SCT8-Board1") (part "FDV303N"))
    )
    (comp (ref "Q25")
      (value "Q")
      (footprint "SOT23-3")
      (description "MOSFET N-CH 25V 680MA SOT-23")
      (fields
        (field (name "02. DISTRIBUTOR PART NUMBER") "FDV303NDKR-ND")
        (field (name "07. MANUFACTURER  PART NUMBER") "FDV303N")
        (field (name "13. CREATED DATE/NAME") "AUG 2018 / Hören")
      )
      (libsource (lib "SCT8-Board1") (part "FDV303N"))
    )
    (comp (ref "Q26")
      (value "Q")
      (footprint "SOT23-3")
      (description "MOSFET N-CH 25V 680MA SOT-23")
      (fields
        (field (name "02. DISTRIBUTOR PART NUMBER") "FDV303NDKR-ND")
        (field (name "07. MANUFACTURER  PART NUMBER") "FDV303N")
        (field (name "13. CREATED DATE/NAME") "AUG 2018 / Hören")
      )
      (libsource (lib "SCT8-Board1") (part "FDV303N"))
    )
    (comp (ref "Q27")
      (value "Q")
      (footprint "SOT23-3")
      (description "MOSFET N-CH 25V 680MA SOT-23")
      (fields
        (field (name "02. DISTRIBUTOR PART NUMBER") "FDV303NDKR-ND")
        (field (name "07. MANUFACTURER  PART NUMBER") "FDV303N")
        (field (name "13. CREATED DATE/NAME") "AUG 2018 / Hören")
      )
      (libsource (lib "SCT8-Board1") (part "FDV303N"))
    )
    (comp (ref "Q28")
      (value "Q")
      (footprint "SOT23-3")
      (description "MOSFET N-CH 25V 680MA SOT-23")
      (fields
        (field (name "02. DISTRIBUTOR PART NUMBER") "FDV303NDKR-ND")
        (field (name "07. MANUFACTURER  PART NUMBER") "FDV303N")
        (field (name "13. CREATED DATE/NAME") "AUG 2018 / Hören")
      )
      (libsource (lib "SCT8-Board1") (part "FDV303N"))
    )
    (comp (ref "Q29")
      (value "Q")
      (footprint "SOT23-3")
      (description "MOSFET N-CH 25V 680MA SOT-23")
      (fields
        (field (name "02. DISTRIBUTOR PART NUMBER") "FDV303NDKR-ND")
        (field (name "07. MANUFACTURER  PART NUMBER") "FDV303N")
        (field (name "13. CREATED DATE/NAME") "AUG 2018 / Hören")
      )
      (libsource (lib "SCT8-Board1") (part "FDV303N"))
    )
    (comp (ref "Q30")
      (value "Q")
      (footprint "SOT23-3")
      (description "MOSFET N-CH 25V 680MA SOT-23")
      (fields
        (field (name "02. DISTRIBUTOR PART NUMBER") "FDV303NDKR-ND")
        (field (name "07. MANUFACTURER  PART NUMBER") "FDV303N")
        (field (name "13. CREATED DATE/NAME") "AUG 2018 / Hören")
      )
      (libsource (lib "SCT8-Board1") (part "FDV303N"))
    )
    (comp (ref "Q31")
      (value "Q")
      (footprint "SOT23-3")
      (description "MOSFET N-CH 25V 680MA SOT-23")
      (fields
        (field (name "02. DISTRIBUTOR PART NUMBER") "FDV303NDKR-ND")
        (field (name "07. MANUFACTURER  PART NUMBER") "FDV303N")
        (field (name "13. CREATED DATE/NAME") "AUG 2018 / Hören")
      )
      (libsource (lib "SCT8-Board1") (part "FDV303N"))
    )
    (comp (ref "Q32")
      (value "Q")
      (footprint "SOT23-3")
      (description "MOSFET N-CH 25V 680MA SOT-23")
      (fields
        (field (name "02. DISTRIBUTOR PART NUMBER") "FDV303NDKR-ND")
        (field (name "07. MANUFACTURER  PART NUMBER") "FDV303N")
        (field (name "13. CREATED DATE/NAME") "AUG 2018 / Hören")
      )
      (libsource (lib "SCT8-Board1") (part "FDV303N"))
    )
    (comp (ref "Q33")
      (value "Q")
      (footprint "SOT23-3")
      (description "MOSFET N-CH 25V 680MA SOT-23")
      (fields
        (field (name "02. DISTRIBUTOR PART NUMBER") "FDV303NDKR-ND")
        (field (name "07. MANUFACTURER  PART NUMBER") "FDV303N")
        (field (name "13. CREATED DATE/NAME") "AUG 2018 / Hören")
      )
      (libsource (lib "SCT8-Board1") (part "FDV303N"))
    )
    (comp (ref "Q34")
      (value "Q")
      (footprint "SOT23-3")
      (description "MOSFET N-CH 25V 680MA SOT-23")
      (fields
        (field (name "02. DISTRIBUTOR PART NUMBER") "FDV303NDKR-ND")
        (field (name "07. MANUFACTURER  PART NUMBER") "FDV303N")
        (field (name "13. CREATED DATE/NAME") "AUG 2018 / Hören")
      )
      (libsource (lib "SCT8-Board1") (part "FDV303N"))
    )
    (comp (ref "Q35")
      (value "Q")
      (footprint "SOT23-3")
      (description "MOSFET N-CH 25V 680MA SOT-23")
      (fields
        (field (name "02. DISTRIBUTOR PART NUMBER") "FDV303NDKR-ND")
        (field (name "07. MANUFACTURER  PART NUMBER") "FDV303N")
        (field (name "13. CREATED DATE/NAME") "AUG 2018 / Hören")
      )
      (libsource (lib "SCT8-Board1") (part "FDV303N"))
    )
    (comp (ref "Q36")
      (value "Q")
      (footprint "SOT23-3")
      (description "MOSFET N-CH 25V 680MA SOT-23")
      (fields
        (field (name "02. DISTRIBUTOR PART NUMBER") "FDV303NDKR-ND")
        (field (name "07. MANUFACTURER  PART NUMBER") "FDV303N")
        (field (name "13. CREATED DATE/NAME") "AUG 2018 / Hören")
      )
      (libsource (lib "SCT8-Board1") (part "FDV303N"))
    )
    (comp (ref "Q37")
      (value "Q")
      (footprint "SOT23-3")
      (description "MOSFET N-CH 25V 680MA SOT-23")
      (fields
        (field (name "02. DISTRIBUTOR PART NUMBER") "FDV303NDKR-ND")
        (field (name "07. MANUFACTURER  PART NUMBER") "FDV303N")
        (field (name "13. CREATED DATE/NAME") "AUG 2018 / Hören")
      )
      (libsource (lib "SCT8-Board1") (part "FDV303N"))
    )
    (comp (ref "Q38")
      (value "Q")
      (footprint "SOT23-3")
      (description "MOSFET N-CH 25V 680MA SOT-23")
      (fields
        (field (name "02. DISTRIBUTOR PART NUMBER") "FDV303NDKR-ND")
        (field (name "07. MANUFACTURER  PART NUMBER") "FDV303N")
        (field (name "13. CREATED DATE/NAME") "AUG 2018 / Hören")
      )
      (libsource (lib "SCT8-Board1") (part "FDV303N"))
    )
    (comp (ref "Q39")
      (value "Q")
      (footprint "SOT23-3")
      (description "MOSFET N-CH 25V 680MA SOT-23")
      (fields
        (field (name "02. DISTRIBUTOR PART NUMBER") "FDV303NDKR-ND")
        (field (name "07. MANUFACTURER  PART NUMBER") "FDV303N")
        (field (name "13. CREATED DATE/NAME") "AUG 2018 / Hören")
      )
      (libsource (lib "SCT8-Board1") (part "FDV303N"))
    )
    (comp (ref "Q40")
      (value "Q")
      (footprint "SOT23-3")
      (description "MOSFET N-CH 25V 680MA SOT-23")
      (fields
        (field (name "02. DISTRIBUTOR PART NUMBER") "FDV303NDKR-ND")
        (field (name "07. MANUFACTURER  PART NUMBER") "FDV303N")
        (field (name "13. CREATED DATE/NAME") "AUG 2018 / Hören")
      )
      (libsource (lib "SCT8-Board1") (part "FDV303N"))
    )
    (comp (ref "Q41")
      (value "Q")
      (footprint "SOT23-3")
      (description "MOSFET N-CH 25V 680MA SOT-23")
      (fields
        (field (name "02. DISTRIBUTOR PART NUMBER") "FDV303NDKR-ND")
        (field (name "07. MANUFACTURER  PART NUMBER") "FDV303N")
        (field (name "13. CREATED DATE/NAME") "AUG 2018 / Hören")
      )
      (libsource (lib "SCT8-Board1") (part "FDV303N"))
    )
    (comp (ref "Q42")
      (value "Q")
      (footprint "SOT23-3")
      (description "MOSFET N-CH 25V 680MA SOT-23")
      (fields
        (field (name "02. DISTRIBUTOR PART NUMBER") "FDV303NDKR-ND")
        (field (name "07. MANUFACTURER  PART NUMBER") "FDV303N")
        (field (name "13. CREATED DATE/NAME") "AUG 2018 / Hören")
      )
      (libsource (lib "SCT8-Board1") (part "FDV303N"))
    )
    (comp (ref "Q43")
      (value "Q")
      (footprint "SOT23-3")
      (description "MOSFET N-CH 25V 680MA SOT-23")
      (fields
        (field (name "02. DISTRIBUTOR PART NUMBER") "FDV303NDKR-ND")
        (field (name "07. MANUFACTURER  PART NUMBER") "FDV303N")
        (field (name "13. CREATED DATE/NAME") "AUG 2018 / Hören")
      )
      (libsource (lib "SCT8-Board1") (part "FDV303N"))
    )
    (comp (ref "Q44")
      (value "Q")
      (footprint "SOT23-3")
      (description "MOSFET N-CH 25V 680MA SOT-23")
      (fields
        (field (name "02. DISTRIBUTOR PART NUMBER") "FDV303NDKR-ND")
        (field (name "07. MANUFACTURER  PART NUMBER") "FDV303N")
        (field (name "13. CREATED DATE/NAME") "AUG 2018 / Hören")
      )
      (libsource (lib "SCT8-Board1") (part "FDV303N"))
    )
    (comp (ref "Q45")
      (value "Q")
      (footprint "SOT23-3")
      (description "MOSFET N-CH 25V 680MA SOT-23")
      (fields
        (field (name "02. DISTRIBUTOR PART NUMBER") "FDV303NDKR-ND")
        (field (name "07. MANUFACTURER  PART NUMBER") "FDV303N")
        (field (name "13. CREATED DATE/NAME") "AUG 2018 / Hören")
      )
      (libsource (lib "SCT8-Board1") (part "FDV303N"))
    )
    (comp (ref "Q46")
      (value "Q")
      (footprint "SOT23-3")
      (description "MOSFET N-CH 25V 680MA SOT-23")
      (fields
        (field (name "02. DISTRIBUTOR PART NUMBER") "FDV303NDKR-ND")
        (field (name "07. MANUFACTURER  PART NUMBER") "FDV303N")
        (field (name "13. CREATED DATE/NAME") "AUG 2018 / Hören")
      )
      (libsource (lib "SCT8-Board1") (part "FDV303N"))
    )
    (comp (ref "Q47")
      (value "Q")
      (footprint "SOT23-3")
      (description "MOSFET N-CH 25V 680MA SOT-23")
      (fields
        (field (name "02. DISTRIBUTOR PART NUMBER") "FDV303NDKR-ND")
        (field (name "07. MANUFACTURER  PART NUMBER") "FDV303N")
        (field (name "13. CREATED DATE/NAME") "AUG 2018 / Hören")
      )
      (libsource (lib "SCT8-Board1") (part "FDV303N"))
    )
    (comp (ref "Q48")
      (value "Q")
      (footprint "SOT23-3")
      (description "MOSFET N-CH 25V 680MA SOT-23")
      (fields
        (field (name "02. DISTRIBUTOR PART NUMBER") "FDV303NDKR-ND")
        (field (name "07. MANUFACTURER  PART NUMBER") "FDV303N")
        (field (name "13. CREATED DATE/NAME") "AUG 2018 / Hören")
      )
      (libsource (lib "SCT8-Board1") (part "FDV303N"))
    )
    (comp (ref "Q49")
      (value "Q")
      (footprint "SOT23-3")
      (description "MOSFET N-CH 25V 680MA SOT-23")
      (fields
        (field (name "02. DISTRIBUTOR PART NUMBER") "FDV303NDKR-ND")
        (field (name "07. MANUFACTURER  PART NUMBER") "FDV303N")
        (field (name "13. CREATED DATE/NAME") "AUG 2018 / Hören")
      )
      (libsource (lib "SCT8-Board1") (part "FDV303N"))
    )
    (comp (ref "Q50")
      (value "Q")
      (footprint "SOT23-3")
      (description "MOSFET N-CH 25V 680MA SOT-23")
      (fields
        (field (name "02. DISTRIBUTOR PART NUMBER") "FDV303NDKR-ND")
        (field (name "07. MANUFACTURER  PART NUMBER") "FDV303N")
        (field (name "13. CREATED DATE/NAME") "AUG 2018 / Hören")
      )
      (libsource (lib "SCT8-Board1") (part "FDV303N"))
    )
    (comp (ref "Q51")
      (value "Q")
      (footprint "SOT23-3")
      (description "MOSFET N-CH 25V 680MA SOT-23")
      (fields
        (field (name "02. DISTRIBUTOR PART NUMBER") "FDV303NDKR-ND")
        (field (name "07. MANUFACTURER  PART NUMBER") "FDV303N")
        (field (name "13. CREATED DATE/NAME") "AUG 2018 / Hören")
      )
      (libsource (lib "SCT8-Board1") (part "FDV303N"))
    )
    (comp (ref "Q52")
      (value "Q")
      (footprint "SOT23-3")
      (description "MOSFET N-CH 25V 680MA SOT-23")
      (fields
        (field (name "02. DISTRIBUTOR PART NUMBER") "FDV303NDKR-ND")
        (field (name "07. MANUFACTURER  PART NUMBER") "FDV303N")
        (field (name "13. CREATED DATE/NAME") "AUG 2018 / Hören")
      )
      (libsource (lib "SCT8-Board1") (part "FDV303N"))
    )
    (comp (ref "Q53")
      (value "Q")
      (footprint "SOT23-3")
      (description "MOSFET N-CH 25V 680MA SOT-23")
      (fields
        (field (name "02. DISTRIBUTOR PART NUMBER") "FDV303NDKR-ND")
        (field (name "07. MANUFACTURER  PART NUMBER") "FDV303N")
        (field (name "13. CREATED DATE/NAME") "AUG 2018 / Hören")
      )
      (libsource (lib "SCT8-Board1") (part "FDV303N"))
    )
    (comp (ref "Q54")
      (value "Q")
      (footprint "SOT23-3")
      (description "MOSFET N-CH 25V 680MA SOT-23")
      (fields
        (field (name "02. DISTRIBUTOR PART NUMBER") "FDV303NDKR-ND")
        (field (name "07. MANUFACTURER  PART NUMBER") "FDV303N")
        (field (name "13. CREATED DATE/NAME") "AUG 2018 / Hören")
      )
      (libsource (lib "SCT8-Board1") (part "FDV303N"))
    )
    (comp (ref "Q55")
      (value "Q")
      (footprint "SOT23-3")
      (description "MOSFET N-CH 25V 680MA SOT-23")
      (fields
        (field (name "02. DISTRIBUTOR PART NUMBER") "FDV303NDKR-ND")
        (field (name "07. MANUFACTURER  PART NUMBER") "FDV303N")
        (field (name "13. CREATED DATE/NAME") "AUG 2018 / Hören")
      )
      (libsource (lib "SCT8-Board1") (part "FDV303N"))
    )
    (comp (ref "Q56")
      (value "Q")
      (footprint "SOT23-3")
      (description "MOSFET N-CH 25V 680MA SOT-23")
      (fields
        (field (name "02. DISTRIBUTOR PART NUMBER") "FDV303NDKR-ND")
        (field (name "07. MANUFACTURER  PART NUMBER") "FDV303N")
        (field (name "13. CREATED DATE/NAME") "AUG 2018 / Hören")
      )
      (libsource (lib "SCT8-Board1") (part "FDV303N"))
    )
    (comp (ref "Q57")
      (value "Q")
      (footprint "SOT23-3")
      (description "MOSFET N-CH 25V 680MA SOT-23")
      (fields
        (field (name "02. DISTRIBUTOR PART NUMBER") "FDV303NDKR-ND")
        (field (name "07. MANUFACTURER  PART NUMBER") "FDV303N")
        (field (name "13. CREATED DATE/NAME") "AUG 2018 / Hören")
      )
      (libsource (lib "SCT8-Board1") (part "FDV303N"))
    )
    (comp (ref "Q58")
      (value "Q")
      (footprint "SOT23-3")
      (description "MOSFET N-CH 25V 680MA SOT-23")
      (fields
        (field (name "02. DISTRIBUTOR PART NUMBER") "FDV303NDKR-ND")
        (field (name "07. MANUFACTURER  PART NUMBER") "FDV303N")
        (field (name "13. CREATED DATE/NAME") "AUG 2018 / Hören")
      )
      (libsource (lib "SCT8-Board1") (part "FDV303N"))
    )
    (comp (ref "Q59")
      (value "Q")
      (footprint "SOT23-3")
      (description "MOSFET N-CH 25V 680MA SOT-23")
      (fields
        (field (name "02. DISTRIBUTOR PART NUMBER") "FDV303NDKR-ND")
        (field (name "07. MANUFACTURER  PART NUMBER") "FDV303N")
        (field (name "13. CREATED DATE/NAME") "AUG 2018 / Hören")
      )
      (libsource (lib "SCT8-Board1") (part "FDV303N"))
    )
    (comp (ref "Q60")
      (value "Q")
      (footprint "SOT23-3")
      (description "MOSFET N-CH 25V 680MA SOT-23")
      (fields
        (field (name "02. DISTRIBUTOR PART NUMBER") "FDV303NDKR-ND")
        (field (name "07. MANUFACTURER  PART NUMBER") "FDV303N")
        (field (name "13. CREATED DATE/NAME") "AUG 2018 / Hören")
      )
      (libsource (lib "SCT8-Board1") (part "FDV303N"))
    )
    (comp (ref "Q61")
      (value "Q")
      (footprint "SOT23-3")
      (description "MOSFET N-CH 25V 680MA SOT-23")
      (fields
        (field (name "02. DISTRIBUTOR PART NUMBER") "FDV303NDKR-ND")
        (field (name "07. MANUFACTURER  PART NUMBER") "FDV303N")
        (field (name "13. CREATED DATE/NAME") "AUG 2018 / Hören")
      )
      (libsource (lib "SCT8-Board1") (part "FDV303N"))
    )
    (comp (ref "Q62")
      (value "Q")
      (footprint "SOT23-3")
      (description "MOSFET N-CH 25V 680MA SOT-23")
      (fields
        (field (name "02. DISTRIBUTOR PART NUMBER") "FDV303NDKR-ND")
        (field (name "07. MANUFACTURER  PART NUMBER") "FDV303N")
        (field (name "13. CREATED DATE/NAME") "AUG 2018 / Hören")
      )
      (libsource (lib "SCT8-Board1") (part "FDV303N"))
    )
    (comp (ref "Q63")
      (value "Q")
      (footprint "SOT23-3")
      (description "MOSFET N-CH 25V 680MA SOT-23")
      (fields
        (field (name "02. DISTRIBUTOR PART NUMBER") "FDV303NDKR-ND")
        (field (name "07. MANUFACTURER  PART NUMBER") "FDV303N")
        (field (name "13. CREATED DATE/NAME") "AUG 2018 / Hören")
      )
      (libsource (lib "SCT8-Board1") (part "FDV303N"))
    )
    (comp (ref "Q64")
      (value "Q")
      (footprint "SOT23-3")
      (description "MOSFET N-CH 25V 680MA SOT-23")
      (fields
        (field (name "02. DISTRIBUTOR PART NUMBER") "FDV303NDKR-ND")
        (field (name "07. MANUFACTURER  PART NUMBER") "FDV303N")
        (field (name "13. CREATED DATE/NAME") "AUG 2018 / Hören")
      )
      (libsource (lib "SCT8-Board1") (part "FDV303N"))
    )
    (comp (ref "R1")
      (value "4K7")
      (footprint "R0402 Reflow")
      (description "Resistor")
      (fields
        (field (name "TOLERANCE") "±1%")
        (field (name "Comment") "R")
        (field (name "13. CREATED DATE/NAME") "AUG2018/Hören")
      )
      (libsource (lib "chickenfood") (part "R"))
    )
    (comp (ref "R2")
      (value "4K7")
      (footprint "R0402 Reflow")
      (description "Resistor")
      (fields
        (field (name "TOLERANCE") "±1%")
        (field (name "Comment") "R")
        (field (name "13. CREATED DATE/NAME") "AUG2018/Hören")
      )
      (libsource (lib "chickenfood") (part "R"))
    )
    (comp (ref "R3")
      (value "4K7")
      (footprint "R0402 Reflow")
      (description "Resistor")
      (fields
        (field (name "TOLERANCE") "±1%")
        (field (name "Comment") "R")
        (field (name "13. CREATED DATE/NAME") "AUG2018/Hören")
      )
      (libsource (lib "chickenfood") (part "R"))
    )
    (comp (ref "R4")
      (value "4K7")
      (footprint "R0402 Reflow")
      (description "Resistor")
      (fields
        (field (name "TOLERANCE") "±1%")
        (field (name "Comment") "R")
        (field (name "13. CREATED DATE/NAME") "AUG2018/Hören")
      )
      (libsource (lib "chickenfood") (part "R"))
    )
    (comp (ref "R5")
      (value "4K7")
      (footprint "R0402 Reflow")
      (description "Resistor")
      (fields
        (field (name "TOLERANCE") "±1%")
        (field (name "Comment") "R")
        (field (name "13. CREATED DATE/NAME") "AUG2018/Hören")
      )
      (libsource (lib "chickenfood") (part "R"))
    )
    (comp (ref "R6")
      (value "4K7")
      (footprint "R0402 Reflow")
      (description "Resistor")
      (fields
        (field (name "TOLERANCE") "±1%")
        (field (name "Comment") "R")
        (field (name "13. CREATED DATE/NAME") "AUG2018/Hören")
      )
      (libsource (lib "chickenfood") (part "R"))
    )
    (comp (ref "R7")
      (value "4K7")
      (footprint "R0402 Reflow")
      (description "Resistor")
      (fields
        (field (name "TOLERANCE") "±1%")
        (field (name "Comment") "R")
        (field (name "13. CREATED DATE/NAME") "AUG2018/Hören")
      )
      (libsource (lib "chickenfood") (part "R"))
    )
    (comp (ref "R8")
      (value "4K7")
      (footprint "R0402 Reflow")
      (description "Resistor")
      (fields
        (field (name "TOLERANCE") "±1%")
        (field (name "Comment") "R")
        (field (name "13. CREATED DATE/NAME") "AUG2018/Hören")
      )
      (libsource (lib "chickenfood") (part "R"))
    )
    (comp (ref "R9")
      (value "4K7")
      (footprint "R0402 Reflow")
      (description "Resistor")
      (fields
        (field (name "TOLERANCE") "±1%")
        (field (name "Comment") "R")
        (field (name "13. CREATED DATE/NAME") "AUG2018/Hören")
      )
      (libsource (lib "chickenfood") (part "R"))
    )
    (comp (ref "R10")
      (value "4K7")
      (footprint "R0402 Reflow")
      (description "Resistor")
      (fields
        (field (name "TOLERANCE") "±1%")
        (field (name "Comment") "R")
        (field (name "13. CREATED DATE/NAME") "AUG2018/Hören")
      )
      (libsource (lib "chickenfood") (part "R"))
    )
    (comp (ref "R11")
      (value "4K7")
      (footprint "R0402 Reflow")
      (description "Resistor")
      (fields
        (field (name "TOLERANCE") "±1%")
        (field (name "Comment") "R")
        (field (name "13. CREATED DATE/NAME") "AUG2018/Hören")
      )
      (libsource (lib "chickenfood") (part "R"))
    )
    (comp (ref "R12")
      (value "4K7")
      (footprint "R0402 Reflow")
      (description "Resistor")
      (fields
        (field (name "TOLERANCE") "±1%")
        (field (name "Comment") "R")
        (field (name "13. CREATED DATE/NAME") "AUG2018/Hören")
      )
      (libsource (lib "chickenfood") (part "R"))
    )
    (comp (ref "R13")
      (value "4K7")
      (footprint "R0402 Reflow")
      (description "Resistor")
      (fields
        (field (name "TOLERANCE") "±1%")
        (field (name "Comment") "R")
        (field (name "13. CREATED DATE/NAME") "AUG2018/Hören")
      )
      (libsource (lib "chickenfood") (part "R"))
    )
    (comp (ref "R14")
      (value "4K7")
      (footprint "R0402 Reflow")
      (description "Resistor")
      (fields
        (field (name "TOLERANCE") "±1%")
        (field (name "Comment") "R")
        (field (name "13. CREATED DATE/NAME") "AUG2018/Hören")
      )
      (libsource (lib "chickenfood") (part "R"))
    )
    (comp (ref "R15")
      (value "4K7")
      (footprint "R0402 Reflow")
      (description "Resistor")
      (fields
        (field (name "TOLERANCE") "±1%")
        (field (name "Comment") "R")
        (field (name "13. CREATED DATE/NAME") "AUG2018/Hören")
      )
      (libsource (lib "chickenfood") (part "R"))
    )
    (comp (ref "R16")
      (value "4K7")
      (footprint "R0402 Reflow")
      (description "Resistor")
      (fields
        (field (name "TOLERANCE") "±1%")
        (field (name "Comment") "R")
        (field (name "13. CREATED DATE/NAME") "AUG2018/Hören")
      )
      (libsource (lib "chickenfood") (part "R"))
    )
    (comp (ref "R17")
      (value "4K7")
      (footprint "R0402 Reflow")
      (description "Resistor")
      (fields
        (field (name "TOLERANCE") "±1%")
        (field (name "Comment") "R")
        (field (name "13. CREATED DATE/NAME") "AUG2018/Hören")
      )
      (libsource (lib "chickenfood") (part "R"))
    )
    (comp (ref "R18")
      (value "4K7")
      (footprint "R0402 Reflow")
      (description "Resistor")
      (fields
        (field (name "TOLERANCE") "±1%")
        (field (name "Comment") "R")
        (field (name "13. CREATED DATE/NAME") "AUG2018/Hören")
      )
      (libsource (lib "chickenfood") (part "R"))
    )
    (comp (ref "R19")
      (value "4K7")
      (footprint "R0402 Reflow")
      (description "Resistor")
      (fields
        (field (name "TOLERANCE") "±1%")
        (field (name "Comment") "R")
        (field (name "13. CREATED DATE/NAME") "AUG2018/Hören")
      )
      (libsource (lib "chickenfood") (part "R"))
    )
    (comp (ref "R20")
      (value "4K7")
      (footprint "R0402 Reflow")
      (description "Resistor")
      (fields
        (field (name "TOLERANCE") "±1%")
        (field (name "Comment") "R")
        (field (name "13. CREATED DATE/NAME") "AUG2018/Hören")
      )
      (libsource (lib "chickenfood") (part "R"))
    )
    (comp (ref "R21")
      (value "4K7")
      (footprint "R0402 Reflow")
      (description "Resistor")
      (fields
        (field (name "TOLERANCE") "±1%")
        (field (name "Comment") "R")
        (field (name "13. CREATED DATE/NAME") "AUG2018/Hören")
      )
      (libsource (lib "chickenfood") (part "R"))
    )
    (comp (ref "R22")
      (value "4K7")
      (footprint "R0402 Reflow")
      (description "Resistor")
      (fields
        (field (name "TOLERANCE") "±1%")
        (field (name "Comment") "R")
        (field (name "13. CREATED DATE/NAME") "AUG2018/Hören")
      )
      (libsource (lib "chickenfood") (part "R"))
    )
    (comp (ref "R23")
      (value "4K7")
      (footprint "R0402 Reflow")
      (description "Resistor")
      (fields
        (field (name "TOLERANCE") "±1%")
        (field (name "Comment") "R")
        (field (name "13. CREATED DATE/NAME") "AUG2018/Hören")
      )
      (libsource (lib "chickenfood") (part "R"))
    )
    (comp (ref "R24")
      (value "4K7")
      (footprint "R0402 Reflow")
      (description "Resistor")
      (fields
        (field (name "TOLERANCE") "±1%")
        (field (name "Comment") "R")
        (field (name "13. CREATED DATE/NAME") "AUG2018/Hören")
      )
      (libsource (lib "chickenfood") (part "R"))
    )
    (comp (ref "R25")
      (value "4K7")
      (footprint "R0402 Reflow")
      (description "Resistor")
      (fields
        (field (name "TOLERANCE") "±1%")
        (field (name "Comment") "R")
        (field (name "13. CREATED DATE/NAME") "AUG2018/Hören")
      )
      (libsource (lib "chickenfood") (part "R"))
    )
    (comp (ref "R26")
      (value "4K7")
      (footprint "R0402 Reflow")
      (description "Resistor")
      (fields
        (field (name "TOLERANCE") "±1%")
        (field (name "Comment") "R")
        (field (name "13. CREATED DATE/NAME") "AUG2018/Hören")
      )
      (libsource (lib "chickenfood") (part "R"))
    )
    (comp (ref "R27")
      (value "4K7")
      (footprint "R0402 Reflow")
      (description "Resistor")
      (fields
        (field (name "TOLERANCE") "±1%")
        (field (name "Comment") "R")
        (field (name "13. CREATED DATE/NAME") "AUG2018/Hören")
      )
      (libsource (lib "chickenfood") (part "R"))
    )
    (comp (ref "R28")
      (value "4K7")
      (footprint "R0402 Reflow")
      (description "Resistor")
      (fields
        (field (name "TOLERANCE") "±1%")
        (field (name "Comment") "R")
        (field (name "13. CREATED DATE/NAME") "AUG2018/Hören")
      )
      (libsource (lib "chickenfood") (part "R"))
    )
    (comp (ref "R29")
      (value "4K7")
      (footprint "R0402 Reflow")
      (description "Resistor")
      (fields
        (field (name "TOLERANCE") "±1%")
        (field (name "Comment") "R")
        (field (name "13. CREATED DATE/NAME") "AUG2018/Hören")
      )
      (libsource (lib "chickenfood") (part "R"))
    )
    (comp (ref "R30")
      (value "4K7")
      (footprint "R0402 Reflow")
      (description "Resistor")
      (fields
        (field (name "TOLERANCE") "±1%")
        (field (name "Comment") "R")
        (field (name "13. CREATED DATE/NAME") "AUG2018/Hören")
      )
      (libsource (lib "chickenfood") (part "R"))
    )
    (comp (ref "R31")
      (value "4K7")
      (footprint "R0402 Reflow")
      (description "Resistor")
      (fields
        (field (name "TOLERANCE") "±1%")
        (field (name "Comment") "R")
        (field (name "13. CREATED DATE/NAME") "AUG2018/Hören")
      )
      (libsource (lib "chickenfood") (part "R"))
    )
    (comp (ref "R32")
      (value "4K7")
      (footprint "R0402 Reflow")
      (description "Resistor")
      (fields
        (field (name "TOLERANCE") "±1%")
        (field (name "Comment") "R")
        (field (name "13. CREATED DATE/NAME") "AUG2018/Hören")
      )
      (libsource (lib "chickenfood") (part "R"))
    )
    (comp (ref "R33")
      (value "4K7")
      (footprint "R0402 Reflow")
      (description "Resistor")
      (fields
        (field (name "TOLERANCE") "±1%")
        (field (name "Comment") "R")
        (field (name "13. CREATED DATE/NAME") "AUG2018/Hören")
      )
      (libsource (lib "chickenfood") (part "R"))
    )
    (comp (ref "R34")
      (value "4K7")
      (footprint "R0402 Reflow")
      (description "Resistor")
      (fields
        (field (name "TOLERANCE") "±1%")
        (field (name "Comment") "R")
        (field (name "13. CREATED DATE/NAME") "AUG2018/Hören")
      )
      (libsource (lib "chickenfood") (part "R"))
    )
    (comp (ref "R35")
      (value "4K7")
      (footprint "R0402 Reflow")
      (description "Resistor")
      (fields
        (field (name "TOLERANCE") "±1%")
        (field (name "Comment") "R")
        (field (name "13. CREATED DATE/NAME") "AUG2018/Hören")
      )
      (libsource (lib "chickenfood") (part "R"))
    )
    (comp (ref "R36")
      (value "4K7")
      (footprint "R0402 Reflow")
      (description "Resistor")
      (fields
        (field (name "TOLERANCE") "±1%")
        (field (name "Comment") "R")
        (field (name "13. CREATED DATE/NAME") "AUG2018/Hören")
      )
      (libsource (lib "chickenfood") (part "R"))
    )
    (comp (ref "R37")
      (value "4K7")
      (footprint "R0402 Reflow")
      (description "Resistor")
      (fields
        (field (name "TOLERANCE") "±1%")
        (field (name "Comment") "R")
        (field (name "13. CREATED DATE/NAME") "AUG2018/Hören")
      )
      (libsource (lib "chickenfood") (part "R"))
    )
    (comp (ref "R38")
      (value "4K7")
      (footprint "R0402 Reflow")
      (description "Resistor")
      (fields
        (field (name "TOLERANCE") "±1%")
        (field (name "Comment") "R")
        (field (name "13. CREATED DATE/NAME") "AUG2018/Hören")
      )
      (libsource (lib "chickenfood") (part "R"))
    )
    (comp (ref "R39")
      (value "4K7")
      (footprint "R0402 Reflow")
      (description "Resistor")
      (fields
        (field (name "TOLERANCE") "±1%")
        (field (name "Comment") "R")
        (field (name "13. CREATED DATE/NAME") "AUG2018/Hören")
      )
      (libsource (lib "chickenfood") (part "R"))
    )
    (comp (ref "R40")
      (value "4K7")
      (footprint "R0402 Reflow")
      (description "Resistor")
      (fields
        (field (name "TOLERANCE") "±1%")
        (field (name "Comment") "R")
        (field (name "13. CREATED DATE/NAME") "AUG2018/Hören")
      )
      (libsource (lib "chickenfood") (part "R"))
    )
    (comp (ref "R41")
      (value "4K7")
      (footprint "R0402 Reflow")
      (description "Resistor")
      (fields
        (field (name "TOLERANCE") "±1%")
        (field (name "Comment") "R")
        (field (name "13. CREATED DATE/NAME") "AUG2018/Hören")
      )
      (libsource (lib "chickenfood") (part "R"))
    )
    (comp (ref "R42")
      (value "4K7")
      (footprint "R0402 Reflow")
      (description "Resistor")
      (fields
        (field (name "TOLERANCE") "±1%")
        (field (name "Comment") "R")
        (field (name "13. CREATED DATE/NAME") "AUG2018/Hören")
      )
      (libsource (lib "chickenfood") (part "R"))
    )
    (comp (ref "R48")
      (value "4K7")
      (footprint "R0402 Reflow")
      (description "Resistor")
      (fields
        (field (name "TOLERANCE") "±1%")
        (field (name "Comment") "R")
        (field (name "13. CREATED DATE/NAME") "AUG2018/Hören")
      )
      (libsource (lib "chickenfood") (part "R"))
    )
    (comp (ref "R49")
      (value "4K7")
      (footprint "R0402 Reflow")
      (description "Resistor")
      (fields
        (field (name "TOLERANCE") "±1%")
        (field (name "Comment") "R")
        (field (name "13. CREATED DATE/NAME") "AUG2018/Hören")
      )
      (libsource (lib "chickenfood") (part "R"))
    )
    (comp (ref "R50")
      (value "4K7")
      (footprint "R0402 Reflow")
      (description "Resistor")
      (fields
        (field (name "TOLERANCE") "±1%")
        (field (name "Comment") "R")
        (field (name "13. CREATED DATE/NAME") "AUG2018/Hören")
      )
      (libsource (lib "chickenfood") (part "R"))
    )
    (comp (ref "R51")
      (value "4K7")
      (footprint "R0402 Reflow")
      (description "Resistor")
      (fields
        (field (name "TOLERANCE") "±1%")
        (field (name "Comment") "R")
        (field (name "13. CREATED DATE/NAME") "AUG2018/Hören")
      )
      (libsource (lib "chickenfood") (part "R"))
    )
    (comp (ref "R52")
      (value "4K7")
      (footprint "R0402 Reflow")
      (description "Resistor")
      (fields
        (field (name "TOLERANCE") "±1%")
        (field (name "Comment") "R")
        (field (name "13. CREATED DATE/NAME") "AUG2018/Hören")
      )
      (libsource (lib "chickenfood") (part "R"))
    )
    (comp (ref "R53")
      (value "4K7")
      (footprint "R0402 Reflow")
      (description "Resistor")
      (fields
        (field (name "TOLERANCE") "±1%")
        (field (name "Comment") "R")
        (field (name "13. CREATED DATE/NAME") "AUG2018/Hören")
      )
      (libsource (lib "chickenfood") (part "R"))
    )
    (comp (ref "R54")
      (value "4K7")
      (footprint "R0402 Reflow")
      (description "Resistor")
      (fields
        (field (name "TOLERANCE") "±1%")
        (field (name "Comment") "R")
        (field (name "13. CREATED DATE/NAME") "AUG2018/Hören")
      )
      (libsource (lib "chickenfood") (part "R"))
    )
    (comp (ref "R55")
      (value "4K7")
      (footprint "R0402 Reflow")
      (description "Resistor")
      (fields
        (field (name "TOLERANCE") "±1%")
        (field (name "Comment") "R")
        (field (name "13. CREATED DATE/NAME") "AUG2018/Hören")
      )
      (libsource (lib "chickenfood") (part "R"))
    )
    (comp (ref "R56")
      (value "4K7")
      (footprint "R0402 Reflow")
      (description "Resistor")
      (fields
        (field (name "TOLERANCE") "±1%")
        (field (name "Comment") "R")
        (field (name "13. CREATED DATE/NAME") "AUG2018/Hören")
      )
      (libsource (lib "chickenfood") (part "R"))
    )
    (comp (ref "R57")
      (value "4K7")
      (footprint "R0402 Reflow")
      (description "Resistor")
      (fields
        (field (name "TOLERANCE") "±1%")
        (field (name "Comment") "R")
        (field (name "13. CREATED DATE/NAME") "AUG2018/Hören")
      )
      (libsource (lib "chickenfood") (part "R"))
    )
    (comp (ref "R58")
      (value "4K7")
      (footprint "R0402 Reflow")
      (description "Resistor")
      (fields
        (field (name "TOLERANCE") "±1%")
        (field (name "Comment") "R")
        (field (name "13. CREATED DATE/NAME") "AUG2018/Hören")
      )
      (libsource (lib "chickenfood") (part "R"))
    )
    (comp (ref "R59")
      (value "4K7")
      (footprint "R0402 Reflow")
      (description "Resistor")
      (fields
        (field (name "TOLERANCE") "±1%")
        (field (name "Comment") "R")
        (field (name "13. CREATED DATE/NAME") "AUG2018/Hören")
      )
      (libsource (lib "chickenfood") (part "R"))
    )
    (comp (ref "R60")
      (value "4K7")
      (footprint "R0402 Reflow")
      (description "Resistor")
      (fields
        (field (name "TOLERANCE") "±1%")
        (field (name "Comment") "R")
        (field (name "13. CREATED DATE/NAME") "AUG2018/Hören")
      )
      (libsource (lib "chickenfood") (part "R"))
    )
    (comp (ref "R61")
      (value "4K7")
      (footprint "R0402 Reflow")
      (description "Resistor")
      (fields
        (field (name "TOLERANCE") "±1%")
        (field (name "Comment") "R")
        (field (name "13. CREATED DATE/NAME") "AUG2018/Hören")
      )
      (libsource (lib "chickenfood") (part "R"))
    )
    (comp (ref "R62")
      (value "4K7")
      (footprint "R0402 Reflow")
      (description "Resistor")
      (fields
        (field (name "TOLERANCE") "±1%")
        (field (name "Comment") "R")
        (field (name "13. CREATED DATE/NAME") "AUG2018/Hören")
      )
      (libsource (lib "chickenfood") (part "R"))
    )
    (comp (ref "R63")
      (value "4K7")
      (footprint "R0402 Reflow")
      (description "Resistor")
      (fields
        (field (name "TOLERANCE") "±1%")
        (field (name "Comment") "R")
        (field (name "13. CREATED DATE/NAME") "AUG2018/Hören")
      )
      (libsource (lib "chickenfood") (part "R"))
    )
    (comp (ref "R64")
      (value "4K7")
      (footprint "R0402 Reflow")
      (description "Resistor")
      (fields
        (field (name "TOLERANCE") "±1%")
        (field (name "Comment") "R")
        (field (name "13. CREATED DATE/NAME") "AUG2018/Hören")
      )
      (libsource (lib "chickenfood") (part "R"))
    )
    (comp (ref "R65")
      (value "4K7")
      (footprint "R0402 Reflow")
      (description "Resistor")
      (fields
        (field (name "TOLERANCE") "±1%")
        (field (name "Comment") "R")
        (field (name "13. CREATED DATE/NAME") "AUG2018/Hören")
      )
      (libsource (lib "chickenfood") (part "R"))
    )
    (comp (ref "R66")
      (value "4K7")
      (footprint "R0402 Reflow")
      (description "Resistor")
      (fields
        (field (name "TOLERANCE") "±1%")
        (field (name "Comment") "R")
        (field (name "13. CREATED DATE/NAME") "AUG2018/Hören")
      )
      (libsource (lib "chickenfood") (part "R"))
    )
    (comp (ref "R67")
      (value "4K7")
      (footprint "R0402 Reflow")
      (description "Resistor")
      (fields
        (field (name "TOLERANCE") "±1%")
        (field (name "Comment") "R")
        (field (name "13. CREATED DATE/NAME") "AUG2018/Hören")
      )
      (libsource (lib "chickenfood") (part "R"))
    )
    (comp (ref "R68")
      (value "4K7")
      (footprint "R0402 Reflow")
      (description "Resistor")
      (fields
        (field (name "TOLERANCE") "±1%")
        (field (name "Comment") "R")
        (field (name "13. CREATED DATE/NAME") "AUG2018/Hören")
      )
      (libsource (lib "chickenfood") (part "R"))
    )
    (comp (ref "R69")
      (value "4K7")
      (footprint "R0402 Reflow")
      (description "Resistor")
      (fields
        (field (name "TOLERANCE") "±1%")
        (field (name "Comment") "R")
        (field (name "13. CREATED DATE/NAME") "AUG2018/Hören")
      )
      (libsource (lib "chickenfood") (part "R"))
    )
    (comp (ref "X1")
      (value "X")
      (description "24 x 2 x 1.27mm SOCKET DISCRETE CABL")
      (fields
        (field (name "02. DISTRIBUTOR PART NUMBER") "SFSD-32-30C-G-15.00-S")
        (field (name "13. CREATED DATE/NAME") "??? / Hören")
      )
      (libsource (lib "PCB-Relay-Board-V1") (part "SFSD-32-30C-G-15.00-S"))
    )
    (comp (ref "X2")
      (value "X")
      (footprint "TFC-132-01-F-D-RA")
      (description "CONN HEADER TH RA 48POS 1.27MM")
      (fields
        (field (name "02. DISTRIBUTOR PART NUMBER") "TFC-132-01-F-D-RA")
        (field (name "13. CREATED DATE/NAME") "??? / Hören")
      )
      (libsource (lib "PCB-Relay-Board-V1") (part "TFC-132-01-F-D-RA"))
    )
    (comp (ref "X3")
      (value "X")
      (footprint "CONFIG64")
      (description "PCB Tester Configuration Matrix for 48 Relays over 8 ABUSes")
      (fields (field (name "13. CREATED DATE/NAME") "??? / Hören"))
      (libsource (lib "PCB-Relay-Board-V1") (part "CONFIG64"))
    )
    (comp (ref "X4")
      (value "X")
      (footprint "PCIE-036-02-F-D-Fingers")
      (description "CONN PCI Card Edge 36POS")
      (libsource (lib "Connectors") (part "PCIE-036-02-F-D-Fingers"))
    )
  )
  (nets
    (net (code "3") (name "/A0") (class "Default")
      (node (ref "X4") (pin "B1") (pinfunction "B1_B1") (pintype "passive"))
    )
    (net (code "4") (name "/A1") (class "Default")
      (node (ref "X4") (pin "B2") (pinfunction "B2_B2") (pintype "passive"))
    )
    (net (code "5") (name "/A2") (class "Default")
      (node (ref "X4") (pin "B3") (pinfunction "B3_B3") (pintype "passive"))
    )
    (net (code "6") (name "/A3") (class "Default")
      (node (ref "X4") (pin "B4") (pinfunction "B4_B4") (pintype "passive"))
    )
    (net (code "7") (name "/ABUS0") (class "Default")
      (node (ref "X3") (pin "ABUS0") (pinfunction "ABUS0_ABUS0") (pintype "passive"))
      (node (ref "X4") (pin "A1") (pinfunction "A1_A1") (pintype "passive"))
    )
    (net (code "8") (name "/ABUS1") (class "Default")
      (node (ref "X3") (pin "ABUS1") (pinfunction "ABUS1_ABUS1") (pintype "passive"))
      (node (ref "X4") (pin "A2") (pinfunction "A2_A2") (pintype "passive"))
    )
    (net (code "9") (name "/ABUS2") (class "Default")
      (node (ref "X3") (pin "ABUS2") (pinfunction "ABUS2_ABUS2") (pintype "passive"))
      (node (ref "X4") (pin "A3") (pinfunction "A3_A3") (pintype "passive"))
    )
    (net (code "10") (name "/ABUS3") (class "Default")
      (node (ref "X3") (pin "ABUS3") (pinfunction "ABUS3_ABUS3") (pintype "passive"))
      (node (ref "X4") (pin "A4") (pinfunction "A4_A4") (pintype "passive"))
    )
    (net (code "11") (name "/ABUS4") (class "Default")
      (node (ref "X3") (pin "ABUS4") (pinfunction "ABUS4_ABUS4") (pintype "passive"))
      (node (ref "X4") (pin "A5") (pinfunction "A5_A5") (pintype "passive"))
    )
    (net (code "12") (name "/ABUS5") (class "Default")
      (node (ref "X3") (pin "ABUS5") (pinfunction "ABUS5_ABUS5") (pintype "passive"))
      (node (ref "X4") (pin "A6") (pinfunction "A6_A6") (pintype "passive"))
    )
    (net (code "13") (name "/ABUS6") (class "Default")
      (node (ref "X3") (pin "ABUS6") (pinfunction "ABUS6_ABUS6") (pintype "passive"))
      (node (ref "X4") (pin "A7") (pinfunction "A7_A7") (pintype "passive"))
    )
    (net (code "14") (name "/ABUS7") (class "Default")
      (node (ref "X3") (pin "ABUS7") (pinfunction "ABUS7_ABUS7") (pintype "passive"))
      (node (ref "X4") (pin "A8") (pinfunction "A8_A8") (pintype "passive"))
    )
    (net (code "16") (name "/CS") (class "Default")
      (node (ref "X4") (pin "B18") (pinfunction "B18_B18") (pintype "passive"))
    )
    (net (code "17") (name "/DRV1") (class "Default")
      (node (ref "Q1") (pin "1") (pinfunction "G_1") (pintype "passive"))
      (node (ref "R1") (pin "2") (pinfunction "2_2") (pintype "passive"))
    )
    (net (code "18") (name "/DRV2") (class "Default")
      (node (ref "Q2") (pin "1") (pinfunction "G_1") (pintype "passive"))
      (node (ref "R2") (pin "2") (pinfunction "2_2") (pintype "passive"))
    )
    (net (code "19") (name "/DRV3") (class "Default")
      (node (ref "Q3") (pin "1") (pinfunction "G_1") (pintype "passive"))
      (node (ref "R3") (pin "2") (pinfunction "2_2") (pintype "passive"))
    )
    (net (code "20") (name "/DRV4") (class "Default")
      (node (ref "Q4") (pin "1") (pinfunction "G_1") (pintype "passive"))
      (node (ref "R4") (pin "2") (pinfunction "2_2") (pintype "passive"))
    )
    (net (code "21") (name "/DRV5") (class "Default")
      (node (ref "Q5") (pin "1") (pinfunction "G_1") (pintype "passive"))
      (node (ref "R5") (pin "2") (pinfunction "2_2") (pintype "passive"))
    )
    (net (code "22") (name "/DRV6") (class "Default")
      (node (ref "Q6") (pin "1") (pinfunction "G_1") (pintype "passive"))
      (node (ref "R6") (pin "2") (pinfunction "2_2") (pintype "passive"))
    )
    (net (code "23") (name "/DRV7") (class "Default")
      (node (ref "Q7") (pin "1") (pinfunction "G_1") (pintype "passive"))
      (node (ref "R7") (pin "2") (pinfunction "2_2") (pintype "passive"))
    )
    (net (code "24") (name "/DRV8") (class "Default")
      (node (ref "Q8") (pin "1") (pinfunction "G_1") (pintype "passive"))
      (node (ref "R8") (pin "2") (pinfunction "2_2") (pintype "passive"))
    )
    (net (code "25") (name "/DRV9") (class "Default")
      (node (ref "Q9") (pin "1") (pinfunction "G_1") (pintype "passive"))
      (node (ref "R9") (pin "2") (pinfunction "2_2") (pintype "passive"))
    )
    (net (code "26") (name "/DRV10") (class "Default")
      (node (ref "Q10") (pin "1") (pinfunction "G_1") (pintype "passive"))
      (node (ref "R10") (pin "2") (pinfunction "2_2") (pintype "passive"))
    )
    (net (code "27") (name "/DRV11") (class "Default")
      (node (ref "Q11") (pin "1") (pinfunction "G_1") (pintype "passive"))
      (node (ref "R11") (pin "2") (pinfunction "2_2") (pintype "passive"))
    )
    (net (code "28") (name "/DRV12") (class "Default")
      (node (ref "Q12") (pin "1") (pinfunction "G_1") (pintype "passive"))
      (node (ref "R12") (pin "2") (pinfunction "2_2") (pintype "passive"))
    )
    (net (code "29") (name "/DRV13") (class "Default")
      (node (ref "Q13") (pin "1") (pinfunction "G_1") (pintype "passive"))
      (node (ref "R13") (pin "2") (pinfunction "2_2") (pintype "passive"))
    )
    (net (code "30") (name "/DRV14") (class "Default")
      (node (ref "Q14") (pin "1") (pinfunction "G_1") (pintype "passive"))
      (node (ref "R14") (pin "2") (pinfunction "2_2") (pintype "passive"))
    )
    (net (code "31") (name "/DRV15") (class "Default")
      (node (ref "Q15") (pin "1") (pinfunction "G_1") (pintype "passive"))
      (node (ref "R15") (pin "2") (pinfunction "2_2") (pintype "passive"))
    )
    (net (code "32") (name "/DRV16") (class "Default")
      (node (ref "Q16") (pin "1") (pinfunction "G_1") (pintype "passive"))
      (node (ref "R16") (pin "2") (pinfunction "2_2") (pintype "passive"))
    )
    (net (code "33") (name "/DRV17") (class "Default")
      (node (ref "Q17") (pin "1") (pinfunction "G_1") (pintype "passive"))
      (node (ref "R17") (pin "2") (pinfunction "2_2") (pintype "passive"))
    )
    (net (code "34") (name "/DRV18") (class "Default")
      (node (ref "Q18") (pin "1") (pinfunction "G_1") (pintype "passive"))
      (node (ref "R18") (pin "2") (pinfunction "2_2") (pintype "passive"))
    )
    (net (code "35") (name "/DRV19") (class "Default")
      (node (ref "Q19") (pin "1") (pinfunction "G_1") (pintype "passive"))
      (node (ref "R19") (pin "2") (pinfunction "2_2") (pintype "passive"))
    )
    (net (code "36") (name "/DRV20") (class "Default")
      (node (ref "Q20") (pin "1") (pinfunction "G_1") (pintype "passive"))
      (node (ref "R20") (pin "2") (pinfunction "2_2") (pintype "passive"))
    )
    (net (code "37") (name "/DRV21") (class "Default")
      (node (ref "Q21") (pin "1") (pinfunction "G_1") (pintype "passive"))
      (node (ref "R21") (pin "2") (pinfunction "2_2") (pintype "passive"))
    )
    (net (code "38") (name "/DRV22") (class "Default")
      (node (ref "Q22") (pin "1") (pinfunction "G_1") (pintype "passive"))
      (node (ref "R22") (pin "2") (pinfunction "2_2") (pintype "passive"))
    )
    (net (code "39") (name "/DRV23") (class "Default")
      (node (ref "Q23") (pin "1") (pinfunction "G_1") (pintype "passive"))
      (node (ref "R23") (pin "2") (pinfunction "2_2") (pintype "passive"))
    )
    (net (code "40") (name "/DRV24") (class "Default")
      (node (ref "Q24") (pin "1") (pinfunction "G_1") (pintype "passive"))
      (node (ref "R24") (pin "2") (pinfunction "2_2") (pintype "passive"))
    )
    (net (code "41") (name "/DRV25") (class "Default")
      (node (ref "Q25") (pin "1") (pinfunction "G_1") (pintype "passive"))
      (node (ref "R25") (pin "2") (pinfunction "2_2") (pintype "passive"))
    )
    (net (code "42") (name "/DRV26") (class "Default")
      (node (ref "Q26") (pin "1") (pinfunction "G_1") (pintype "passive"))
      (node (ref "R26") (pin "2") (pinfunction "2_2") (pintype "passive"))
    )
    (net (code "43") (name "/DRV27") (class "Default")
      (node (ref "Q27") (pin "1") (pinfunction "G_1") (pintype "passive"))
      (node (ref "R27") (pin "2") (pinfunction "2_2") (pintype "passive"))
    )
    (net (code "44") (name "/DRV28") (class "Default")
      (node (ref "Q28") (pin "1") (pinfunction "G_1") (pintype "passive"))
      (node (ref "R28") (pin "2") (pinfunction "2_2") (pintype "passive"))
    )
    (net (code "45") (name "/DRV29") (class "Default")
      (node (ref "Q29") (pin "1") (pinfunction "G_1") (pintype "passive"))
      (node (ref "R29") (pin "2") (pinfunction "2_2") (pintype "passive"))
    )
    (net (code "46") (name "/DRV30") (class "Default")
      (node (ref "Q30") (pin "1") (pinfunction "G_1") (pintype "passive"))
      (node (ref "R30") (pin "2") (pinfunction "2_2") (pintype "passive"))
    )
    (net (code "47") (name "/DRV31") (class "Default")
      (node (ref "Q31") (pin "1") (pinfunction "G_1") (pintype "passive"))
      (node (ref "R31") (pin "2") (pinfunction "2_2") (pintype "passive"))
    )
    (net (code "48") (name "/DRV32") (class "Default")
      (node (ref "Q32") (pin "1") (pinfunction "G_1") (pintype "passive"))
      (node (ref "R32") (pin "2") (pinfunction "2_2") (pintype "passive"))
    )
    (net (code "49") (name "/DRV33") (class "Default")
      (node (ref "Q33") (pin "1") (pinfunction "G_1") (pintype "passive"))
      (node (ref "R33") (pin "2") (pinfunction "2_2") (pintype "passive"))
    )
    (net (code "50") (name "/DRV34") (class "Default")
      (node (ref "Q34") (pin "1") (pinfunction "G_1") (pintype "passive"))
      (node (ref "R34") (pin "2") (pinfunction "2_2") (pintype "passive"))
    )
    (net (code "51") (name "/DRV35") (class "Default")
      (node (ref "Q35") (pin "1") (pinfunction "G_1") (pintype "passive"))
      (node (ref "R35") (pin "2") (pinfunction "2_2") (pintype "passive"))
    )
    (net (code "52") (name "/DRV36") (class "Default")
      (node (ref "Q36") (pin "1") (pinfunction "G_1") (pintype "passive"))
      (node (ref "R36") (pin "2") (pinfunction "2_2") (pintype "passive"))
    )
    (net (code "53") (name "/DRV37") (class "Default")
      (node (ref "Q37") (pin "1") (pinfunction "G_1") (pintype "passive"))
      (node (ref "R37") (pin "2") (pinfunction "2_2") (pintype "passive"))
    )
    (net (code "54") (name "/DRV38") (class "Default")
      (node (ref "Q38") (pin "1") (pinfunction "G_1") (pintype "passive"))
      (node (ref "R38") (pin "2") (pinfunction "2_2") (pintype "passive"))
    )
    (net (code "55") (name "/DRV39") (class "Default")
      (node (ref "Q39") (pin "1") (pinfunction "G_1") (pintype "passive"))
      (node (ref "R39") (pin "2") (pinfunction "2_2") (pintype "passive"))
    )
    (net (code "56") (name "/DRV40") (class "Default")
      (node (ref "Q40") (pin "1") (pinfunction "G_1") (pintype "passive"))
      (node (ref "R40") (pin "2") (pinfunction "2_2") (pintype "passive"))
    )
    (net (code "57") (name "/DRV41") (class "Default")
      (node (ref "Q41") (pin "1") (pinfunction "G_1") (pintype "passive"))
      (node (ref "R41") (pin "2") (pinfunction "2_2") (pintype "passive"))
    )
    (net (code "58") (name "/DRV42") (class "Default")
      (node (ref "Q42") (pin "1") (pinfunction "G_1") (pintype "passive"))
      (node (ref "R42") (pin "2") (pinfunction "2_2") (pintype "passive"))
    )
    (net (code "59") (name "/DRV43") (class "Default")
      (node (ref "Q43") (pin "1") (pinfunction "G_1") (pintype "passive"))
      (node (ref "R48") (pin "2") (pinfunction "2_2") (pintype "passive"))
    )
    (net (code "60") (name "/DRV44") (class "Default")
      (node (ref "Q44") (pin "1") (pinfunction "G_1") (pintype "passive"))
      (node (ref "R49") (pin "2") (pinfunction "2_2") (pintype "passive"))
    )
    (net (code "61") (name "/DRV45") (class "Default")
      (node (ref "Q45") (pin "1") (pinfunction "G_1") (pintype "passive"))
      (node (ref "R50") (pin "2") (pinfunction "2_2") (pintype "passive"))
    )
    (net (code "62") (name "/DRV46") (class "Default")
      (node (ref "Q46") (pin "1") (pinfunction "G_1") (pintype "passive"))
      (node (ref "R51") (pin "2") (pinfunction "2_2") (pintype "passive"))
    )
    (net (code "63") (name "/DRV47") (class "Default")
      (node (ref "Q47") (pin "1") (pinfunction "G_1") (pintype "passive"))
      (node (ref "R52") (pin "2") (pinfunction "2_2") (pintype "passive"))
    )
    (net (code "64") (name "/DRV48") (class "Default")
      (node (ref "Q48") (pin "1") (pinfunction "G_1") (pintype "passive"))
      (node (ref "R53") (pin "2") (pinfunction "2_2") (pintype "passive"))
    )
    (net (code "65") (name "/DRV49") (class "Default")
      (node (ref "Q49") (pin "1") (pinfunction "G_1") (pintype "passive"))
      (node (ref "R54") (pin "2") (pinfunction "2_2") (pintype "passive"))
    )
    (net (code "66") (name "/DRV50") (class "Default")
      (node (ref "Q50") (pin "1") (pinfunction "G_1") (pintype "passive"))
      (node (ref "R55") (pin "2") (pinfunction "2_2") (pintype "passive"))
    )
    (net (code "67") (name "/DRV51") (class "Default")
      (node (ref "Q51") (pin "1") (pinfunction "G_1") (pintype "passive"))
      (node (ref "R56") (pin "2") (pinfunction "2_2") (pintype "passive"))
    )
    (net (code "68") (name "/DRV52") (class "Default")
      (node (ref "Q52") (pin "1") (pinfunction "G_1") (pintype "passive"))
      (node (ref "R57") (pin "2") (pinfunction "2_2") (pintype "passive"))
    )
    (net (code "69") (name "/DRV53") (class "Default")
      (node (ref "Q53") (pin "1") (pinfunction "G_1") (pintype "passive"))
      (node (ref "R58") (pin "2") (pinfunction "2_2") (pintype "passive"))
    )
    (net (code "70") (name "/DRV54") (class "Default")
      (node (ref "Q54") (pin "1") (pinfunction "G_1") (pintype "passive"))
      (node (ref "R59") (pin "2") (pinfunction "2_2") (pintype "passive"))
    )
    (net (code "71") (name "/DRV55") (class "Default")
      (node (ref "Q55") (pin "1") (pinfunction "G_1") (pintype "passive"))
      (node (ref "R60") (pin "2") (pinfunction "2_2") (pintype "passive"))
    )
    (net (code "72") (name "/DRV56") (class "Default")
      (node (ref "Q56") (pin "1") (pinfunction "G_1") (pintype "passive"))
      (node (ref "R61") (pin "2") (pinfunction "2_2") (pintype "passive"))
    )
    (net (code "73") (name "/DRV57") (class "Default")
      (node (ref "Q57") (pin "1") (pinfunction "G_1") (pintype "passive"))
      (node (ref "R62") (pin "2") (pinfunction "2_2") (pintype "passive"))
    )
    (net (code "74") (name "/DRV58") (class "Default")
      (node (ref "Q58") (pin "1") (pinfunction "G_1") (pintype "passive"))
      (node (ref "R63") (pin "2") (pinfunction "2_2") (pintype "passive"))
    )
    (net (code "75") (name "/DRV59") (class "Default")
      (node (ref "Q59") (pin "1") (pinfunction "G_1") (pintype "passive"))
      (node (ref "R64") (pin "2") (pinfunction "2_2") (pintype "passive"))
    )
    (net (code "76") (name "/DRV60") (class "Default")
      (node (ref "Q60") (pin "1") (pinfunction "G_1") (pintype "passive"))
      (node (ref "R65") (pin "2") (pinfunction "2_2") (pintype "passive"))
    )
    (net (code "77") (name "/DRV61") (class "Default")
      (node (ref "Q61") (pin "1") (pinfunction "G_1") (pintype "passive"))
      (node (ref "R66") (pin "2") (pinfunction "2_2") (pintype "passive"))
    )
    (net (code "78") (name "/DRV62") (class "Default")
      (node (ref "Q62") (pin "1") (pinfunction "G_1") (pintype "passive"))
      (node (ref "R67") (pin "2") (pinfunction "2_2") (pintype "passive"))
    )
    (net (code "79") (name "/DRV63") (class "Default")
      (node (ref "Q63") (pin "1") (pinfunction "G_1") (pintype "passive"))
      (node (ref "R68") (pin "2") (pinfunction "2_2") (pintype "passive"))
    )
    (net (code "80") (name "/DRV64") (class "Default")
      (node (ref "Q64") (pin "1") (pinfunction "G_1") (pintype "passive"))
      (node (ref "R69") (pin "2") (pinfunction "2_2") (pintype "passive"))
    )
    (net (code "82") (name "/MISO") (class "Default")
      (node (ref "X4") (pin "A18") (pinfunction "A18_A18") (pintype "passive"))
    )
    (net (code "83") (name "/MOSI") (class "Default")
      (node (ref "X4") (pin "A17") (pinfunction "A17_A17") (pintype "passive"))
    )
    (net (code "84") (name "/SCLK") (class "Default")
      (node (ref "X4") (pin "B17") (pinfunction "B17_B17") (pintype "passive"))
    )
    (net (code "87") (name "1V0") (class "Default")
      (node (ref "D1") (pin "1") (pinfunction "A_1") (pintype "passive"))
    )
    (net (code "88") (name "1V8") (class "Default")
      (node (ref "D1") (pin "2") (pinfunction "C_2") (pintype "passive"))
      (node (ref "D2") (pin "1") (pinfunction "A_1") (pintype "passive"))
    )
    (net (code "89") (name "2V5") (class "Default")
      (node (ref "D2") (pin "2") (pinfunction "C_2") (pintype "passive"))
      (node (ref "D3") (pin "1") (pinfunction "A_1") (pintype "passive"))
    )
    (net (code "90") (name "3V3") (class "Default")
      (node (ref "D3") (pin "2") (pinfunction "C_2") (pintype "passive"))
      (node (ref "D4") (pin "1") (pinfunction "A_1") (pintype "passive"))
    )
    (net (code "91") (name "5V0R") (class "Default")
      (node (ref "D4") (pin "2") (pinfunction "C_2") (pintype "passive"))
      (node (ref "K1") (pin "1") (pinfunction "+_1") (pintype "passive"))
      (node (ref "K10") (pin "1") (pinfunction "+_1") (pintype "passive"))
      (node (ref "K11") (pin "1") (pinfunction "+_1") (pintype "passive"))
      (node (ref "K12") (pin "1") (pinfunction "+_1") (pintype "passive"))
      (node (ref "K13") (pin "1") (pinfunction "+_1") (pintype "passive"))
      (node (ref "K14") (pin "1") (pinfunction "+_1") (pintype "passive"))
      (node (ref "K15") (pin "1") (pinfunction "+_1") (pintype "passive"))
      (node (ref "K16") (pin "1") (pinfunction "+_1") (pintype "passive"))
      (node (ref "K17") (pin "1") (pinfunction "+_1") (pintype "passive"))
      (node (ref "K18") (pin "1") (pinfunction "+_1") (pintype "passive"))
      (node (ref "K19") (pin "1") (pinfunction "+_1") (pintype "passive"))
      (node (ref "K2") (pin "1") (pinfunction "+_1") (pintype "passive"))
      (node (ref "K20") (pin "1") (pinfunction "+_1") (pintype "passive"))
      (node (ref "K21") (pin "1") (pinfunction "+_1") (pintype "passive"))
      (node (ref "K22") (pin "1") (pinfunction "+_1") (pintype "passive"))
      (node (ref "K23") (pin "1") (pinfunction "+_1") (pintype "passive"))
      (node (ref "K24") (pin "1") (pinfunction "+_1") (pintype "passive"))
      (node (ref "K25") (pin "1") (pinfunction "+_1") (pintype "passive"))
      (node (ref "K26") (pin "1") (pinfunction "+_1") (pintype "passive"))
      (node (ref "K27") (pin "1") (pinfunction "+_1") (pintype "passive"))
      (node (ref "K28") (pin "1") (pinfunction "+_1") (pintype "passive"))
      (node (ref "K29") (pin "1") (pinfunction "+_1") (pintype "passive"))
      (node (ref "K3") (pin "1") (pinfunction "+_1") (pintype "passive"))
      (node (ref "K30") (pin "1") (pinfunction "+_1") (pintype "passive"))
      (node (ref "K31") (pin "1") (pinfunction "+_1") (pintype "passive"))
      (node (ref "K32") (pin "1") (pinfunction "+_1") (pintype "passive"))
      (node (ref "K33") (pin "1") (pinfunction "+_1") (pintype "passive"))
      (node (ref "K34") (pin "1") (pinfunction "+_1") (pintype "passive"))
      (node (ref "K35") (pin "1") (pinfunction "+_1") (pintype "passive"))
      (node (ref "K36") (pin "1") (pinfunction "+_1") (pintype "passive"))
      (node (ref "K37") (pin "1") (pinfunction "+_1") (pintype "passive"))
      (node (ref "K38") (pin "1") (pinfunction "+_1") (pintype "passive"))
      (node (ref "K39") (pin "1") (pinfunction "+_1") (pintype "passive"))
      (node (ref "K4") (pin "1") (pinfunction "+_1") (pintype "passive"))
      (node (ref "K40") (pin "1") (pinfunction "+_1") (pintype "passive"))
      (node (ref "K41") (pin "1") (pinfunction "+_1") (pintype "passive"))
      (node (ref "K42") (pin "1") (pinfunction "+_1") (pintype "passive"))
      (node (ref "K43") (pin "1") (pinfunction "+_1") (pintype "passive"))
      (node (ref "K44") (pin "1") (pinfunction "+_1") (pintype "passive"))
      (node (ref "K45") (pin "1") (pinfunction "+_1") (pintype "passive"))
      (node (ref "K46") (pin "1") (pinfunction "+_1") (pintype "passive"))
      (node (ref "K47") (pin "1") (pinfunction "+_1") (pintype "passive"))
      (node (ref "K48") (pin "1") (pinfunction "+_1") (pintype "passive"))
      (node (ref "K49") (pin "1") (pinfunction "+_1") (pintype "passive"))
      (node (ref "K5") (pin "1") (pinfunction "+_1") (pintype "passive"))
      (node (ref "K50") (pin "1") (pinfunction "+_1") (pintype "passive"))
      (node (ref "K51") (pin "1") (pinfunction "+_1") (pintype "passive"))
      (node (ref "K52") (pin "1") (pinfunction "+_1") (pintype "passive"))
      (node (ref "K53") (pin "1") (pinfunction "+_1") (pintype "passive"))
      (node (ref "K54") (pin "1") (pinfunction "+_1") (pintype "passive"))
      (node (ref "K55") (pin "1") (pinfunction "+_1") (pintype "passive"))
      (node (ref "K56") (pin "1") (pinfunction "+_1") (pintype "passive"))
      (node (ref "K57") (pin "1") (pinfunction "+_1") (pintype "passive"))
      (node (ref "K58") (pin "1") (pinfunction "+_1") (pintype "passive"))
      (node (ref "K59") (pin "1") (pinfunction "+_1") (pintype "passive"))
      (node (ref "K6") (pin "1") (pinfunction "+_1") (pintype "passive"))
      (node (ref "K60") (pin "1") (pinfunction "+_1") (pintype "passive"))
      (node (ref "K61") (pin "1") (pinfunction "+_1") (pintype "passive"))
      (node (ref "K62") (pin "1") (pinfunction "+_1") (pintype "passive"))
      (node (ref "K63") (pin "1") (pinfunction "+_1") (pintype "passive"))
      (node (ref "K64") (pin "1") (pinfunction "+_1") (pintype "passive"))
      (node (ref "K7") (pin "1") (pinfunction "+_1") (pintype "passive"))
      (node (ref "K8") (pin "1") (pinfunction "+_1") (pintype "passive"))
      (node (ref "K9") (pin "1") (pinfunction "+_1") (pintype "passive"))
      (node (ref "X4") (pin "B10") (pinfunction "B10_B10") (pintype "passive"))
      (node (ref "X4") (pin "B11") (pinfunction "B11_B11") (pintype "passive"))
      (node (ref "X4") (pin "B12") (pinfunction "B12_B12") (pintype "passive"))
      (node (ref "X4") (pin "B13") (pinfunction "B13_B13") (pintype "passive"))
      (node (ref "X4") (pin "B14") (pinfunction "B14_B14") (pintype "passive"))
      (node (ref "X4") (pin "B15") (pinfunction "B15_B15") (pintype "passive"))
      (node (ref "X4") (pin "B16") (pinfunction "B16_B16") (pintype "passive"))
      (node (ref "X4") (pin "B9") (pinfunction "B9_B9") (pintype "passive"))
    )
    (net (code "92") (name "12V0") (class "Default")
      (node (ref "X4") (pin "B5") (pinfunction "B5_B5") (pintype "passive"))
      (node (ref "X4") (pin "B6") (pinfunction "B6_B6") (pintype "passive"))
      (node (ref "X4") (pin "B7") (pinfunction "B7_B7") (pintype "passive"))
      (node (ref "X4") (pin "B8") (pinfunction "B8_B8") (pintype "passive"))
    )
    (net (code "93") (name "GND") (class "Default")
      (node (ref "Q1") (pin "2") (pinfunction "S_2") (pintype "passive"))
      (node (ref "Q10") (pin "2") (pinfunction "S_2") (pintype "passive"))
      (node (ref "Q11") (pin "2") (pinfunction "S_2") (pintype "passive"))
      (node (ref "Q12") (pin "2") (pinfunction "S_2") (pintype "passive"))
      (node (ref "Q13") (pin "2") (pinfunction "S_2") (pintype "passive"))
      (node (ref "Q14") (pin "2") (pinfunction "S_2") (pintype "passive"))
      (node (ref "Q15") (pin "2") (pinfunction "S_2") (pintype "passive"))
      (node (ref "Q16") (pin "2") (pinfunction "S_2") (pintype "passive"))
      (node (ref "Q17") (pin "2") (pinfunction "S_2") (pintype "passive"))
      (node (ref "Q18") (pin "2") (pinfunction "S_2") (pintype "passive"))
      (node (ref "Q19") (pin "2") (pinfunction "S_2") (pintype "passive"))
      (node (ref "Q2") (pin "2") (pinfunction "S_2") (pintype "passive"))
      (node (ref "Q20") (pin "2") (pinfunction "S_2") (pintype "passive"))
      (node (ref "Q21") (pin "2") (pinfunction "S_2") (pintype "passive"))
      (node (ref "Q22") (pin "2") (pinfunction "S_2") (pintype "passive"))
      (node (ref "Q23") (pin "2") (pinfunction "S_2") (pintype "passive"))
      (node (ref "Q24") (pin "2") (pinfunction "S_2") (pintype "passive"))
      (node (ref "Q25") (pin "2") (pinfunction "S_2") (pintype "passive"))
      (node (ref "Q26") (pin "2") (pinfunction "S_2") (pintype "passive"))
      (node (ref "Q27") (pin "2") (pinfunction "S_2") (pintype "passive"))
      (node (ref "Q28") (pin "2") (pinfunction "S_2") (pintype "passive"))
      (node (ref "Q29") (pin "2") (pinfunction "S_2") (pintype "passive"))
      (node (ref "Q3") (pin "2") (pinfunction "S_2") (pintype "passive"))
      (node (ref "Q30") (pin "2") (pinfunction "S_2") (pintype "passive"))
      (node (ref "Q31") (pin "2") (pinfunction "S_2") (pintype "passive"))
      (node (ref "Q32") (pin "2") (pinfunction "S_2") (pintype "passive"))
      (node (ref "Q33") (pin "2") (pinfunction "S_2") (pintype "passive"))
      (node (ref "Q34") (pin "2") (pinfunction "S_2") (pintype "passive"))
      (node (ref "Q35") (pin "2") (pinfunction "S_2") (pintype "passive"))
      (node (ref "Q36") (pin "2") (pinfunction "S_2") (pintype "passive"))
      (node (ref "Q37") (pin "2") (pinfunction "S_2") (pintype "passive"))
      (node (ref "Q38") (pin "2") (pinfunction "S_2") (pintype "passive"))
      (node (ref "Q39") (pin "2") (pinfunction "S_2") (pintype "passive"))
      (node (ref "Q4") (pin "2") (pinfunction "S_2") (pintype "passive"))
      (node (ref "Q40") (pin "2") (pinfunction "S_2") (pintype "passive"))
      (node (ref "Q41") (pin "2") (pinfunction "S_2") (pintype "passive"))
      (node (ref "Q42") (pin "2") (pinfunction "S_2") (pintype "passive"))
      (node (ref "Q43") (pin "2") (pinfunction "S_2") (pintype "passive"))
      (node (ref "Q44") (pin "2") (pinfunction "S_2") (pintype "passive"))
      (node (ref "Q45") (pin "2") (pinfunction "S_2") (pintype "passive"))
      (node (ref "Q46") (pin "2") (pinfunction "S_2") (pintype "passive"))
      (node (ref "Q47") (pin "2") (pinfunction "S_2") (pintype "passive"))
      (node (ref "Q48") (pin "2") (pinfunction "S_2") (pintype "passive"))
      (node (ref "Q49") (pin "2") (pinfunction "S_2") (pintype "passive"))
      (node (ref "Q5") (pin "2") (pinfunction "S_2") (pintype "passive"))
      (node (ref "Q50") (pin "2") (pinfunction "S_2") (pintype "passive"))
      (node (ref "Q51") (pin "2") (pinfunction "S_2") (pintype "passive"))
      (node (ref "Q52") (pin "2") (pinfunction "S_2") (pintype "passive"))
      (node (ref "Q53") (pin "2") (pinfunction "S_2") (pintype "passive"))
      (node (ref "Q54") (pin "2") (pinfunction "S_2") (pintype "passive"))
      (node (ref "Q55") (pin "2") (pinfunction "S_2") (pintype "passive"))
      (node (ref "Q56") (pin "2") (pinfunction "S_2") (pintype "passive"))
      (node (ref "Q57") (pin "2") (pinfunction "S_2") (pintype "passive"))
      (node (ref "Q58") (pin "2") (pinfunction "S_2") (pintype "passive"))
      (node (ref "Q59") (pin "2") (pinfunction "S_2") (pintype "passive"))
      (node (ref "Q6") (pin "2") (pinfunction "S_2") (pintype "passive"))
      (node (ref "Q60") (pin "2") (pinfunction "S_2") (pintype "passive"))
      (node (ref "Q61") (pin "2") (pinfunction "S_2") (pintype "passive"))
      (node (ref "Q62") (pin "2") (pinfunction "S_2") (pintype "passive"))
      (node (ref "Q63") (pin "2") (pinfunction "S_2") (pintype "passive"))
      (node (ref "Q64") (pin "2") (pinfunction "S_2") (pintype "passive"))
      (node (ref "Q7") (pin "2") (pinfunction "S_2") (pintype "passive"))
      (node (ref "Q8") (pin "2") (pinfunction "S_2") (pintype "passive"))
      (node (ref "Q9") (pin "2") (pinfunction "S_2") (pintype "passive"))
      (node (ref "R1") (pin "1") (pinfunction "1_1") (pintype "passive"))
      (node (ref "R10") (pin "1") (pinfunction "1_1") (pintype "passive"))
      (node (ref "R11") (pin "1") (pinfunction "1_1") (pintype "passive"))
      (node (ref "R12") (pin "1") (pinfunction "1_1") (pintype "passive"))
      (node (ref "R13") (pin "1") (pinfunction "1_1") (pintype "passive"))
      (node (ref "R14") (pin "1") (pinfunction "1_1") (pintype "passive"))
      (node (ref "R15") (pin "1") (pinfunction "1_1") (pintype "passive"))
      (node (ref "R16") (pin "1") (pinfunction "1_1") (pintype "passive"))
      (node (ref "R17") (pin "1") (pinfunction "1_1") (pintype "passive"))
      (node (ref "R18") (pin "1") (pinfunction "1_1") (pintype "passive"))
      (node (ref "R19") (pin "1") (pinfunction "1_1") (pintype "passive"))
      (node (ref "R2") (pin "1") (pinfunction "1_1") (pintype "passive"))
      (node (ref "R20") (pin "1") (pinfunction "1_1") (pintype "passive"))
      (node (ref "R21") (pin "1") (pinfunction "1_1") (pintype "passive"))
      (node (ref "R22") (pin "1") (pinfunction "1_1") (pintype "passive"))
      (node (ref "R23") (pin "1") (pinfunction "1_1") (pintype "passive"))
      (node (ref "R24") (pin "1") (pinfunction "1_1") (pintype "passive"))
      (node (ref "R25") (pin "1") (pinfunction "1_1") (pintype "passive"))
      (node (ref "R26") (pin "1") (pinfunction "1_1") (pintype "passive"))
      (node (ref "R27") (pin "1") (pinfunction "1_1") (pintype "passive"))
      (node (ref "R28") (pin "1") (pinfunction "1_1") (pintype "passive"))
      (node (ref "R29") (pin "1") (pinfunction "1_1") (pintype "passive"))
      (node (ref "R3") (pin "1") (pinfunction "1_1") (pintype "passive"))
      (node (ref "R30") (pin "1") (pinfunction "1_1") (pintype "passive"))
      (node (ref "R31") (pin "1") (pinfunction "1_1") (pintype "passive"))
      (node (ref "R32") (pin "1") (pinfunction "1_1") (pintype "passive"))
      (node (ref "R33") (pin "1") (pinfunction "1_1") (pintype "passive"))
      (node (ref "R34") (pin "1") (pinfunction "1_1") (pintype "passive"))
      (node (ref "R35") (pin "1") (pinfunction "1_1") (pintype "passive"))
      (node (ref "R36") (pin "1") (pinfunction "1_1") (pintype "passive"))
      (node (ref "R37") (pin "1") (pinfunction "1_1") (pintype "passive"))
      (node (ref "R38") (pin "1") (pinfunction "1_1") (pintype "passive"))
      (node (ref "R39") (pin "1") (pinfunction "1_1") (pintype "passive"))
      (node (ref "R4") (pin "1") (pinfunction "1_1") (pintype "passive"))
      (node (ref "R40") (pin "1") (pinfunction "1_1") (pintype "passive"))
      (node (ref "R41") (pin "1") (pinfunction "1_1") (pintype "passive"))
      (node (ref "R42") (pin "1") (pinfunction "1_1") (pintype "passive"))
      (node (ref "R48") (pin "1") (pinfunction "1_1") (pintype "passive"))
      (node (ref "R49") (pin "1") (pinfunction "1_1") (pintype "passive"))
      (node (ref "R5") (pin "1") (pinfunction "1_1") (pintype "passive"))
      (node (ref "R50") (pin "1") (pinfunction "1_1") (pintype "passive"))
      (node (ref "R51") (pin "1") (pinfunction "1_1") (pintype "passive"))
      (node (ref "R52") (pin "1") (pinfunction "1_1") (pintype "passive"))
      (node (ref "R53") (pin "1") (pinfunction "1_1") (pintype "passive"))
      (node (ref "R54") (pin "1") (pinfunction "1_1") (pintype "passive"))
      (node (ref "R55") (pin "1") (pinfunction "1_1") (pintype "passive"))
      (node (ref "R56") (pin "1") (pinfunction "1_1") (pintype "passive"))
      (node (ref "R57") (pin "1") (pinfunction "1_1") (pintype "passive"))
      (node (ref "R58") (pin "1") (pinfunction "1_1") (pintype "passive"))
      (node (ref "R59") (pin "1") (pinfunction "1_1") (pintype "passive"))
      (node (ref "R6") (pin "1") (pinfunction "1_1") (pintype "passive"))
      (node (ref "R60") (pin "1") (pinfunction "1_1") (pintype "passive"))
      (node (ref "R61") (pin "1") (pinfunction "1_1") (pintype "passive"))
      (node (ref "R62") (pin "1") (pinfunction "1_1") (pintype "passive"))
      (node (ref "R63") (pin "1") (pinfunction "1_1") (pintype "passive"))
      (node (ref "R64") (pin "1") (pinfunction "1_1") (pintype "passive"))
      (node (ref "R65") (pin "1") (pinfunction "1_1") (pintype "passive"))
      (node (ref "R66") (pin "1") (pinfunction "1_1") (pintype "passive"))
      (node (ref "R67") (pin "1") (pinfunction "1_1") (pintype "passive"))
      (node (ref "R68") (pin "1") (pinfunction "1_1") (pintype "passive"))
      (node (ref "R69") (pin "1") (pinfunction "1_1") (pintype "passive"))
      (node (ref "R7") (pin "1") (pinfunction "1_1") (pintype "passive"))
      (node (ref "R8") (pin "1") (pinfunction "1_1") (pintype "passive"))
      (node (ref "R9") (pin "1") (pinfunction "1_1") (pintype "passive"))
      (node (ref "X4") (pin "A10") (pinfunction "A10_A10") (pintype "passive"))
      (node (ref "X4") (pin "A11") (pinfunction "A11_A11") (pintype "passive"))
      (node (ref "X4") (pin "A12") (pinfunction "A12_A12") (pintype "passive"))
      (node (ref "X4") (pin "A13") (pinfunction "A13_A13") (pintype "passive"))
      (node (ref "X4") (pin "A14") (pinfunction "A14_A14") (pintype "passive"))
      (node (ref "X4") (pin "A15") (pinfunction "A15_A15") (pintype "passive"))
      (node (ref "X4") (pin "A16") (pinfunction "A16_A16") (pintype "passive"))
      (node (ref "X4") (pin "A9") (pinfunction "A9_A9") (pintype "passive"))
    )
    (net (code "94") (name "Net-(K1A-CA)") (class "Default")
      (node (ref "K1") (pin "3") (pinfunction "CA_3") (pintype "passive"))
      (node (ref "X3") (pin "1") (pinfunction "1_1") (pintype "passive"))
    )
    (net (code "95") (name "Net-(K1A-CB)") (class "Default")
      (node (ref "K1") (pin "4") (pinfunction "CB_4") (pintype "passive"))
      (node (ref "X2") (pin "1") (pinfunction "1_1") (pintype "passive"))
    )
    (net (code "96") (name "Net-(K1B--)") (class "Default")
      (node (ref "K1") (pin "2") (pinfunction "-_2") (pintype "passive"))
      (node (ref "Q1") (pin "3") (pinfunction "D_3") (pintype "passive"))
    )
    (net (code "97") (name "Net-(K2A-CA)") (class "Default")
      (node (ref "K2") (pin "3") (pinfunction "CA_3") (pintype "passive"))
      (node (ref "X3") (pin "2") (pinfunction "2_2") (pintype "passive"))
    )
    (net (code "98") (name "Net-(K2A-CB)") (class "Default")
      (node (ref "K2") (pin "4") (pinfunction "CB_4") (pintype "passive"))
      (node (ref "X2") (pin "2") (pinfunction "2_2") (pintype "passive"))
    )
    (net (code "99") (name "Net-(K2B--)") (class "Default")
      (node (ref "K2") (pin "2") (pinfunction "-_2") (pintype "passive"))
      (node (ref "Q2") (pin "3") (pinfunction "D_3") (pintype "passive"))
    )
    (net (code "100") (name "Net-(K3A-CA)") (class "Default")
      (node (ref "K3") (pin "3") (pinfunction "CA_3") (pintype "passive"))
      (node (ref "X3") (pin "3") (pinfunction "3_3") (pintype "passive"))
    )
    (net (code "101") (name "Net-(K3A-CB)") (class "Default")
      (node (ref "K3") (pin "4") (pinfunction "CB_4") (pintype "passive"))
      (node (ref "X2") (pin "3") (pinfunction "3_3") (pintype "passive"))
    )
    (net (code "102") (name "Net-(K3B--)") (class "Default")
      (node (ref "K3") (pin "2") (pinfunction "-_2") (pintype "passive"))
      (node (ref "Q3") (pin "3") (pinfunction "D_3") (pintype "passive"))
    )
    (net (code "103") (name "Net-(K4A-CA)") (class "Default")
      (node (ref "K4") (pin "3") (pinfunction "CA_3") (pintype "passive"))
      (node (ref "X3") (pin "4") (pinfunction "4_4") (pintype "passive"))
    )
    (net (code "104") (name "Net-(K4A-CB)") (class "Default")
      (node (ref "K4") (pin "4") (pinfunction "CB_4") (pintype "passive"))
      (node (ref "X2") (pin "4") (pinfunction "4_4") (pintype "passive"))
    )
    (net (code "105") (name "Net-(K4B--)") (class "Default")
      (node (ref "K4") (pin "2") (pinfunction "-_2") (pintype "passive"))
      (node (ref "Q4") (pin "3") (pinfunction "D_3") (pintype "passive"))
    )
    (net (code "106") (name "Net-(K5A-CA)") (class "Default")
      (node (ref "K5") (pin "3") (pinfunction "CA_3") (pintype "passive"))
      (node (ref "X3") (pin "5") (pinfunction "5_5") (pintype "passive"))
    )
    (net (code "107") (name "Net-(K5A-CB)") (class "Default")
      (node (ref "K5") (pin "4") (pinfunction "CB_4") (pintype "passive"))
      (node (ref "X2") (pin "5") (pinfunction "5_5") (pintype "passive"))
    )
    (net (code "108") (name "Net-(K5B--)") (class "Default")
      (node (ref "K5") (pin "2") (pinfunction "-_2") (pintype "passive"))
      (node (ref "Q5") (pin "3") (pinfunction "D_3") (pintype "passive"))
    )
    (net (code "109") (name "Net-(K6A-CA)") (class "Default")
      (node (ref "K6") (pin "3") (pinfunction "CA_3") (pintype "passive"))
      (node (ref "X3") (pin "6") (pinfunction "6_6") (pintype "passive"))
    )
    (net (code "110") (name "Net-(K6A-CB)") (class "Default")
      (node (ref "K6") (pin "4") (pinfunction "CB_4") (pintype "passive"))
      (node (ref "X2") (pin "6") (pinfunction "6_6") (pintype "passive"))
    )
    (net (code "111") (name "Net-(K6B--)") (class "Default")
      (node (ref "K6") (pin "2") (pinfunction "-_2") (pintype "passive"))
      (node (ref "Q6") (pin "3") (pinfunction "D_3") (pintype "passive"))
    )
    (net (code "112") (name "Net-(K7A-CA)") (class "Default")
      (node (ref "K7") (pin "3") (pinfunction "CA_3") (pintype "passive"))
      (node (ref "X3") (pin "7") (pinfunction "7_7") (pintype "passive"))
    )
    (net (code "113") (name "Net-(K7A-CB)") (class "Default")
      (node (ref "K7") (pin "4") (pinfunction "CB_4") (pintype "passive"))
      (node (ref "X2") (pin "7") (pinfunction "7_7") (pintype "passive"))
    )
    (net (code "114") (name "Net-(K7B--)") (class "Default")
      (node (ref "K7") (pin "2") (pinfunction "-_2") (pintype "passive"))
      (node (ref "Q7") (pin "3") (pinfunction "D_3") (pintype "passive"))
    )
    (net (code "115") (name "Net-(K8A-CA)") (class "Default")
      (node (ref "K8") (pin "3") (pinfunction "CA_3") (pintype "passive"))
      (node (ref "X3") (pin "8") (pinfunction "8_8") (pintype "passive"))
    )
    (net (code "116") (name "Net-(K8A-CB)") (class "Default")
      (node (ref "K8") (pin "4") (pinfunction "CB_4") (pintype "passive"))
      (node (ref "X2") (pin "8") (pinfunction "8_8") (pintype "passive"))
    )
    (net (code "117") (name "Net-(K8B--)") (class "Default")
      (node (ref "K8") (pin "2") (pinfunction "-_2") (pintype "passive"))
      (node (ref "Q8") (pin "3") (pinfunction "D_3") (pintype "passive"))
    )
    (net (code "118") (name "Net-(K9A-CA)") (class "Default")
      (node (ref "K9") (pin "3") (pinfunction "CA_3") (pintype "passive"))
      (node (ref "X3") (pin "9") (pinfunction "9_9") (pintype "passive"))
    )
    (net (code "119") (name "Net-(K9A-CB)") (class "Default")
      (node (ref "K9") (pin "4") (pinfunction "CB_4") (pintype "passive"))
      (node (ref "X2") (pin "9") (pinfunction "9_9") (pintype "passive"))
    )
    (net (code "120") (name "Net-(K9B--)") (class "Default")
      (node (ref "K9") (pin "2") (pinfunction "-_2") (pintype "passive"))
      (node (ref "Q9") (pin "3") (pinfunction "D_3") (pintype "passive"))
    )
    (net (code "121") (name "Net-(K10A-CA)") (class "Default")
      (node (ref "K10") (pin "3") (pinfunction "CA_3") (pintype "passive"))
      (node (ref "X3") (pin "10") (pinfunction "10_10") (pintype "passive"))
    )
    (net (code "122") (name "Net-(K10A-CB)") (class "Default")
      (node (ref "K10") (pin "4") (pinfunction "CB_4") (pintype "passive"))
      (node (ref "X2") (pin "10") (pinfunction "10_10") (pintype "passive"))
    )
    (net (code "123") (name "Net-(K10B--)") (class "Default")
      (node (ref "K10") (pin "2") (pinfunction "-_2") (pintype "passive"))
      (node (ref "Q10") (pin "3") (pinfunction "D_3") (pintype "passive"))
    )
    (net (code "124") (name "Net-(K11A-CA)") (class "Default")
      (node (ref "K11") (pin "3") (pinfunction "CA_3") (pintype "passive"))
      (node (ref "X3") (pin "11") (pinfunction "11_11") (pintype "passive"))
    )
    (net (code "125") (name "Net-(K11A-CB)") (class "Default")
      (node (ref "K11") (pin "4") (pinfunction "CB_4") (pintype "passive"))
      (node (ref "X2") (pin "11") (pinfunction "11_11") (pintype "passive"))
    )
    (net (code "126") (name "Net-(K11B--)") (class "Default")
      (node (ref "K11") (pin "2") (pinfunction "-_2") (pintype "passive"))
      (node (ref "Q11") (pin "3") (pinfunction "D_3") (pintype "passive"))
    )
    (net (code "127") (name "Net-(K12A-CA)") (class "Default")
      (node (ref "K12") (pin "3") (pinfunction "CA_3") (pintype "passive"))
      (node (ref "X3") (pin "12") (pinfunction "12_12") (pintype "passive"))
    )
    (net (code "128") (name "Net-(K12A-CB)") (class "Default")
      (node (ref "K12") (pin "4") (pinfunction "CB_4") (pintype "passive"))
      (node (ref "X2") (pin "12") (pinfunction "12_12") (pintype "passive"))
    )
    (net (code "129") (name "Net-(K12B--)") (class "Default")
      (node (ref "K12") (pin "2") (pinfunction "-_2") (pintype "passive"))
      (node (ref "Q12") (pin "3") (pinfunction "D_3") (pintype "passive"))
    )
    (net (code "130") (name "Net-(K13A-CA)") (class "Default")
      (node (ref "K13") (pin "3") (pinfunction "CA_3") (pintype "passive"))
      (node (ref "X3") (pin "13") (pinfunction "13_13") (pintype "passive"))
    )
    (net (code "131") (name "Net-(K13A-CB)") (class "Default")
      (node (ref "K13") (pin "4") (pinfunction "CB_4") (pintype "passive"))
      (node (ref "X2") (pin "13") (pinfunction "13_13") (pintype "passive"))
    )
    (net (code "132") (name "Net-(K13B--)") (class "Default")
      (node (ref "K13") (pin "2") (pinfunction "-_2") (pintype "passive"))
      (node (ref "Q13") (pin "3") (pinfunction "D_3") (pintype "passive"))
    )
    (net (code "133") (name "Net-(K14A-CA)") (class "Default")
      (node (ref "K14") (pin "3") (pinfunction "CA_3") (pintype "passive"))
      (node (ref "X3") (pin "14") (pinfunction "14_14") (pintype "passive"))
    )
    (net (code "134") (name "Net-(K14A-CB)") (class "Default")
      (node (ref "K14") (pin "4") (pinfunction "CB_4") (pintype "passive"))
      (node (ref "X2") (pin "14") (pinfunction "14_14") (pintype "passive"))
    )
    (net (code "135") (name "Net-(K14B--)") (class "Default")
      (node (ref "K14") (pin "2") (pinfunction "-_2") (pintype "passive"))
      (node (ref "Q14") (pin "3") (pinfunction "D_3") (pintype "passive"))
    )
    (net (code "136") (name "Net-(K15A-CA)") (class "Default")
      (node (ref "K15") (pin "3") (pinfunction "CA_3") (pintype "passive"))
      (node (ref "X3") (pin "15") (pinfunction "15_15") (pintype "passive"))
    )
    (net (code "137") (name "Net-(K15A-CB)") (class "Default")
      (node (ref "K15") (pin "4") (pinfunction "CB_4") (pintype "passive"))
      (node (ref "X2") (pin "15") (pinfunction "15_15") (pintype "passive"))
    )
    (net (code "138") (name "Net-(K15B--)") (class "Default")
      (node (ref "K15") (pin "2") (pinfunction "-_2") (pintype "passive"))
      (node (ref "Q15") (pin "3") (pinfunction "D_3") (pintype "passive"))
    )
    (net (code "139") (name "Net-(K16A-CA)") (class "Default")
      (node (ref "K16") (pin "3") (pinfunction "CA_3") (pintype "passive"))
      (node (ref "X3") (pin "16") (pinfunction "16_16") (pintype "passive"))
    )
    (net (code "140") (name "Net-(K16A-CB)") (class "Default")
      (node (ref "K16") (pin "4") (pinfunction "CB_4") (pintype "passive"))
      (node (ref "X2") (pin "16") (pinfunction "16_16") (pintype "passive"))
    )
    (net (code "141") (name "Net-(K16B--)") (class "Default")
      (node (ref "K16") (pin "2") (pinfunction "-_2") (pintype "passive"))
      (node (ref "Q16") (pin "3") (pinfunction "D_3") (pintype "passive"))
    )
    (net (code "142") (name "Net-(K17A-CA)") (class "Default")
      (node (ref "K17") (pin "3") (pinfunction "CA_3") (pintype "passive"))
      (node (ref "X3") (pin "17") (pinfunction "17_17") (pintype "passive"))
    )
    (net (code "143") (name "Net-(K17A-CB)") (class "Default")
      (node (ref "K17") (pin "4") (pinfunction "CB_4") (pintype "passive"))
      (node (ref "X2") (pin "17") (pinfunction "17_17") (pintype "passive"))
    )
    (net (code "144") (name "Net-(K17B--)") (class "Default")
      (node (ref "K17") (pin "2") (pinfunction "-_2") (pintype "passive"))
      (node (ref "Q17") (pin "3") (pinfunction "D_3") (pintype "passive"))
    )
    (net (code "145") (name "Net-(K18A-CA)") (class "Default")
      (node (ref "K18") (pin "3") (pinfunction "CA_3") (pintype "passive"))
      (node (ref "X3") (pin "18") (pinfunction "18_18") (pintype "passive"))
    )
    (net (code "146") (name "Net-(K18A-CB)") (class "Default")
      (node (ref "K18") (pin "4") (pinfunction "CB_4") (pintype "passive"))
      (node (ref "X2") (pin "18") (pinfunction "18_18") (pintype "passive"))
    )
    (net (code "147") (name "Net-(K18B--)") (class "Default")
      (node (ref "K18") (pin "2") (pinfunction "-_2") (pintype "passive"))
      (node (ref "Q18") (pin "3") (pinfunction "D_3") (pintype "passive"))
    )
    (net (code "148") (name "Net-(K19A-CA)") (class "Default")
      (node (ref "K19") (pin "3") (pinfunction "CA_3") (pintype "passive"))
      (node (ref "X3") (pin "19") (pinfunction "19_19") (pintype "passive"))
    )
    (net (code "149") (name "Net-(K19A-CB)") (class "Default")
      (node (ref "K19") (pin "4") (pinfunction "CB_4") (pintype "passive"))
      (node (ref "X2") (pin "19") (pinfunction "19_19") (pintype "passive"))
    )
    (net (code "150") (name "Net-(K19B--)") (class "Default")
      (node (ref "K19") (pin "2") (pinfunction "-_2") (pintype "passive"))
      (node (ref "Q19") (pin "3") (pinfunction "D_3") (pintype "passive"))
    )
    (net (code "151") (name "Net-(K20A-CA)") (class "Default")
      (node (ref "K20") (pin "3") (pinfunction "CA_3") (pintype "passive"))
      (node (ref "X3") (pin "20") (pinfunction "20_20") (pintype "passive"))
    )
    (net (code "152") (name "Net-(K20A-CB)") (class "Default")
      (node (ref "K20") (pin "4") (pinfunction "CB_4") (pintype "passive"))
      (node (ref "X2") (pin "20") (pinfunction "20_20") (pintype "passive"))
    )
    (net (code "153") (name "Net-(K20B--)") (class "Default")
      (node (ref "K20") (pin "2") (pinfunction "-_2") (pintype "passive"))
      (node (ref "Q20") (pin "3") (pinfunction "D_3") (pintype "passive"))
    )
    (net (code "154") (name "Net-(K21A-CA)") (class "Default")
      (node (ref "K21") (pin "3") (pinfunction "CA_3") (pintype "passive"))
      (node (ref "X3") (pin "21") (pinfunction "21_21") (pintype "passive"))
    )
    (net (code "155") (name "Net-(K21A-CB)") (class "Default")
      (node (ref "K21") (pin "4") (pinfunction "CB_4") (pintype "passive"))
      (node (ref "X2") (pin "21") (pinfunction "21_21") (pintype "passive"))
    )
    (net (code "156") (name "Net-(K21B--)") (class "Default")
      (node (ref "K21") (pin "2") (pinfunction "-_2") (pintype "passive"))
      (node (ref "Q21") (pin "3") (pinfunction "D_3") (pintype "passive"))
    )
    (net (code "157") (name "Net-(K22A-CA)") (class "Default")
      (node (ref "K22") (pin "3") (pinfunction "CA_3") (pintype "passive"))
      (node (ref "X3") (pin "22") (pinfunction "22_22") (pintype "passive"))
    )
    (net (code "158") (name "Net-(K22A-CB)") (class "Default")
      (node (ref "K22") (pin "4") (pinfunction "CB_4") (pintype "passive"))
      (node (ref "X2") (pin "22") (pinfunction "22_22") (pintype "passive"))
    )
    (net (code "159") (name "Net-(K22B--)") (class "Default")
      (node (ref "K22") (pin "2") (pinfunction "-_2") (pintype "passive"))
      (node (ref "Q22") (pin "3") (pinfunction "D_3") (pintype "passive"))
    )
    (net (code "160") (name "Net-(K23A-CA)") (class "Default")
      (node (ref "K23") (pin "3") (pinfunction "CA_3") (pintype "passive"))
      (node (ref "X3") (pin "23") (pinfunction "23_23") (pintype "passive"))
    )
    (net (code "161") (name "Net-(K23A-CB)") (class "Default")
      (node (ref "K23") (pin "4") (pinfunction "CB_4") (pintype "passive"))
      (node (ref "X2") (pin "23") (pinfunction "23_23") (pintype "passive"))
    )
    (net (code "162") (name "Net-(K23B--)") (class "Default")
      (node (ref "K23") (pin "2") (pinfunction "-_2") (pintype "passive"))
      (node (ref "Q23") (pin "3") (pinfunction "D_3") (pintype "passive"))
    )
    (net (code "163") (name "Net-(K24A-CA)") (class "Default")
      (node (ref "K24") (pin "3") (pinfunction "CA_3") (pintype "passive"))
      (node (ref "X3") (pin "24") (pinfunction "24_24") (pintype "passive"))
    )
    (net (code "164") (name "Net-(K24A-CB)") (class "Default")
      (node (ref "K24") (pin "4") (pinfunction "CB_4") (pintype "passive"))
      (node (ref "X2") (pin "24") (pinfunction "24_24") (pintype "passive"))
    )
    (net (code "165") (name "Net-(K24B--)") (class "Default")
      (node (ref "K24") (pin "2") (pinfunction "-_2") (pintype "passive"))
      (node (ref "Q24") (pin "3") (pinfunction "D_3") (pintype "passive"))
    )
    (net (code "166") (name "Net-(K25A-CA)") (class "Default")
      (node (ref "K25") (pin "3") (pinfunction "CA_3") (pintype "passive"))
      (node (ref "X3") (pin "25") (pinfunction "25_25") (pintype "passive"))
    )
    (net (code "167") (name "Net-(K25A-CB)") (class "Default")
      (node (ref "K25") (pin "4") (pinfunction "CB_4") (pintype "passive"))
      (node (ref "X2") (pin "25") (pinfunction "25_25") (pintype "passive"))
    )
    (net (code "168") (name "Net-(K25B--)") (class "Default")
      (node (ref "K25") (pin "2") (pinfunction "-_2") (pintype "passive"))
      (node (ref "Q25") (pin "3") (pinfunction "D_3") (pintype "passive"))
    )
    (net (code "169") (name "Net-(K26A-CA)") (class "Default")
      (node (ref "K26") (pin "3") (pinfunction "CA_3") (pintype "passive"))
      (node (ref "X3") (pin "26") (pinfunction "26_26") (pintype "passive"))
    )
    (net (code "170") (name "Net-(K26A-CB)") (class "Default")
      (node (ref "K26") (pin "4") (pinfunction "CB_4") (pintype "passive"))
      (node (ref "X2") (pin "26") (pinfunction "26_26") (pintype "passive"))
    )
    (net (code "171") (name "Net-(K26B--)") (class "Default")
      (node (ref "K26") (pin "2") (pinfunction "-_2") (pintype "passive"))
      (node (ref "Q26") (pin "3") (pinfunction "D_3") (pintype "passive"))
    )
    (net (code "172") (name "Net-(K27A-CA)") (class "Default")
      (node (ref "K27") (pin "3") (pinfunction "CA_3") (pintype "passive"))
      (node (ref "X3") (pin "27") (pinfunction "27_27") (pintype "passive"))
    )
    (net (code "173") (name "Net-(K27A-CB)") (class "Default")
      (node (ref "K27") (pin "4") (pinfunction "CB_4") (pintype "passive"))
      (node (ref "X2") (pin "27") (pinfunction "27_27") (pintype "passive"))
    )
    (net (code "174") (name "Net-(K27B--)") (class "Default")
      (node (ref "K27") (pin "2") (pinfunction "-_2") (pintype "passive"))
      (node (ref "Q27") (pin "3") (pinfunction "D_3") (pintype "passive"))
    )
    (net (code "175") (name "Net-(K28A-CA)") (class "Default")
      (node (ref "K28") (pin "3") (pinfunction "CA_3") (pintype "passive"))
      (node (ref "X3") (pin "28") (pinfunction "28_28") (pintype "passive"))
    )
    (net (code "176") (name "Net-(K28A-CB)") (class "Default")
      (node (ref "K28") (pin "4") (pinfunction "CB_4") (pintype "passive"))
      (node (ref "X2") (pin "28") (pinfunction "28_28") (pintype "passive"))
    )
    (net (code "177") (name "Net-(K28B--)") (class "Default")
      (node (ref "K28") (pin "2") (pinfunction "-_2") (pintype "passive"))
      (node (ref "Q28") (pin "3") (pinfunction "D_3") (pintype "passive"))
    )
    (net (code "178") (name "Net-(K29A-CA)") (class "Default")
      (node (ref "K29") (pin "3") (pinfunction "CA_3") (pintype "passive"))
      (node (ref "X3") (pin "29") (pinfunction "29_29") (pintype "passive"))
    )
    (net (code "179") (name "Net-(K29A-CB)") (class "Default")
      (node (ref "K29") (pin "4") (pinfunction "CB_4") (pintype "passive"))
      (node (ref "X2") (pin "29") (pinfunction "29_29") (pintype "passive"))
    )
    (net (code "180") (name "Net-(K29B--)") (class "Default")
      (node (ref "K29") (pin "2") (pinfunction "-_2") (pintype "passive"))
      (node (ref "Q29") (pin "3") (pinfunction "D_3") (pintype "passive"))
    )
    (net (code "181") (name "Net-(K30A-CA)") (class "Default")
      (node (ref "K30") (pin "3") (pinfunction "CA_3") (pintype "passive"))
      (node (ref "X3") (pin "30") (pinfunction "30_30") (pintype "passive"))
    )
    (net (code "182") (name "Net-(K30A-CB)") (class "Default")
      (node (ref "K30") (pin "4") (pinfunction "CB_4") (pintype "passive"))
      (node (ref "X2") (pin "30") (pinfunction "30_30") (pintype "passive"))
    )
    (net (code "183") (name "Net-(K30B--)") (class "Default")
      (node (ref "K30") (pin "2") (pinfunction "-_2") (pintype "passive"))
      (node (ref "Q30") (pin "3") (pinfunction "D_3") (pintype "passive"))
    )
    (net (code "184") (name "Net-(K31A-CA)") (class "Default")
      (node (ref "K31") (pin "3") (pinfunction "CA_3") (pintype "passive"))
      (node (ref "X3") (pin "31") (pinfunction "31_31") (pintype "passive"))
    )
    (net (code "185") (name "Net-(K31A-CB)") (class "Default")
      (node (ref "K31") (pin "4") (pinfunction "CB_4") (pintype "passive"))
      (node (ref "X2") (pin "31") (pinfunction "31_31") (pintype "passive"))
    )
    (net (code "186") (name "Net-(K31B--)") (class "Default")
      (node (ref "K31") (pin "2") (pinfunction "-_2") (pintype "passive"))
      (node (ref "Q31") (pin "3") (pinfunction "D_3") (pintype "passive"))
    )
    (net (code "187") (name "Net-(K32A-CA)") (class "Default")
      (node (ref "K32") (pin "3") (pinfunction "CA_3") (pintype "passive"))
      (node (ref "X3") (pin "32") (pinfunction "32_32") (pintype "passive"))
    )
    (net (code "188") (name "Net-(K32A-CB)") (class "Default")
      (node (ref "K32") (pin "4") (pinfunction "CB_4") (pintype "passive"))
      (node (ref "X2") (pin "32") (pinfunction "32_32") (pintype "passive"))
    )
    (net (code "189") (name "Net-(K32B--)") (class "Default")
      (node (ref "K32") (pin "2") (pinfunction "-_2") (pintype "passive"))
      (node (ref "Q32") (pin "3") (pinfunction "D_3") (pintype "passive"))
    )
    (net (code "190") (name "Net-(K33A-CA)") (class "Default")
      (node (ref "K33") (pin "3") (pinfunction "CA_3") (pintype "passive"))
      (node (ref "X3") (pin "33") (pinfunction "33_33") (pintype "passive"))
    )
    (net (code "191") (name "Net-(K33A-CB)") (class "Default")
      (node (ref "K33") (pin "4") (pinfunction "CB_4") (pintype "passive"))
      (node (ref "X2") (pin "33") (pinfunction "33_33") (pintype "passive"))
    )
    (net (code "192") (name "Net-(K33B--)") (class "Default")
      (node (ref "K33") (pin "2") (pinfunction "-_2") (pintype "passive"))
      (node (ref "Q33") (pin "3") (pinfunction "D_3") (pintype "passive"))
    )
    (net (code "193") (name "Net-(K34A-CA)") (class "Default")
      (node (ref "K34") (pin "3") (pinfunction "CA_3") (pintype "passive"))
      (node (ref "X3") (pin "34") (pinfunction "34_34") (pintype "passive"))
    )
    (net (code "194") (name "Net-(K34A-CB)") (class "Default")
      (node (ref "K34") (pin "4") (pinfunction "CB_4") (pintype "passive"))
      (node (ref "X2") (pin "34") (pinfunction "34_34") (pintype "passive"))
    )
    (net (code "195") (name "Net-(K34B--)") (class "Default")
      (node (ref "K34") (pin "2") (pinfunction "-_2") (pintype "passive"))
      (node (ref "Q34") (pin "3") (pinfunction "D_3") (pintype "passive"))
    )
    (net (code "196") (name "Net-(K35A-CA)") (class "Default")
      (node (ref "K35") (pin "3") (pinfunction "CA_3") (pintype "passive"))
      (node (ref "X3") (pin "35") (pinfunction "35_35") (pintype "passive"))
    )
    (net (code "197") (name "Net-(K35A-CB)") (class "Default")
      (node (ref "K35") (pin "4") (pinfunction "CB_4") (pintype "passive"))
      (node (ref "X2") (pin "35") (pinfunction "35_35") (pintype "passive"))
    )
    (net (code "198") (name "Net-(K35B--)") (class "Default")
      (node (ref "K35") (pin "2") (pinfunction "-_2") (pintype "passive"))
      (node (ref "Q35") (pin "3") (pinfunction "D_3") (pintype "passive"))
    )
    (net (code "199") (name "Net-(K36A-CA)") (class "Default")
      (node (ref "K36") (pin "3") (pinfunction "CA_3") (pintype "passive"))
      (node (ref "X3") (pin "36") (pinfunction "36_36") (pintype "passive"))
    )
    (net (code "200") (name "Net-(K36A-CB)") (class "Default")
      (node (ref "K36") (pin "4") (pinfunction "CB_4") (pintype "passive"))
      (node (ref "X2") (pin "36") (pinfunction "36_36") (pintype "passive"))
    )
    (net (code "201") (name "Net-(K36B--)") (class "Default")
      (node (ref "K36") (pin "2") (pinfunction "-_2") (pintype "passive"))
      (node (ref "Q36") (pin "3") (pinfunction "D_3") (pintype "passive"))
    )
    (net (code "202") (name "Net-(K37A-CA)") (class "Default")
      (node (ref "K37") (pin "3") (pinfunction "CA_3") (pintype "passive"))
      (node (ref "X3") (pin "37") (pinfunction "37_37") (pintype "passive"))
    )
    (net (code "203") (name "Net-(K37A-CB)") (class "Default")
      (node (ref "K37") (pin "4") (pinfunction "CB_4") (pintype "passive"))
      (node (ref "X2") (pin "37") (pinfunction "37_37") (pintype "passive"))
    )
    (net (code "204") (name "Net-(K37B--)") (class "Default")
      (node (ref "K37") (pin "2") (pinfunction "-_2") (pintype "passive"))
      (node (ref "Q37") (pin "3") (pinfunction "D_3") (pintype "passive"))
    )
    (net (code "205") (name "Net-(K38A-CA)") (class "Default")
      (node (ref "K38") (pin "3") (pinfunction "CA_3") (pintype "passive"))
      (node (ref "X3") (pin "38") (pinfunction "38_38") (pintype "passive"))
    )
    (net (code "206") (name "Net-(K38A-CB)") (class "Default")
      (node (ref "K38") (pin "4") (pinfunction "CB_4") (pintype "passive"))
      (node (ref "X2") (pin "38") (pinfunction "38_38") (pintype "passive"))
    )
    (net (code "207") (name "Net-(K38B--)") (class "Default")
      (node (ref "K38") (pin "2") (pinfunction "-_2") (pintype "passive"))
      (node (ref "Q38") (pin "3") (pinfunction "D_3") (pintype "passive"))
    )
    (net (code "208") (name "Net-(K39A-CA)") (class "Default")
      (node (ref "K39") (pin "3") (pinfunction "CA_3") (pintype "passive"))
      (node (ref "X3") (pin "39") (pinfunction "39_39") (pintype "passive"))
    )
    (net (code "209") (name "Net-(K39A-CB)") (class "Default")
      (node (ref "K39") (pin "4") (pinfunction "CB_4") (pintype "passive"))
      (node (ref "X2") (pin "39") (pinfunction "39_39") (pintype "passive"))
    )
    (net (code "210") (name "Net-(K39B--)") (class "Default")
      (node (ref "K39") (pin "2") (pinfunction "-_2") (pintype "passive"))
      (node (ref "Q39") (pin "3") (pinfunction "D_3") (pintype "passive"))
    )
    (net (code "211") (name "Net-(K40A-CA)") (class "Default")
      (node (ref "K40") (pin "3") (pinfunction "CA_3") (pintype "passive"))
      (node (ref "X3") (pin "40") (pinfunction "40_40") (pintype "passive"))
    )
    (net (code "212") (name "Net-(K40A-CB)") (class "Default")
      (node (ref "K40") (pin "4") (pinfunction "CB_4") (pintype "passive"))
      (node (ref "X2") (pin "40") (pinfunction "40_40") (pintype "passive"))
    )
    (net (code "213") (name "Net-(K40B--)") (class "Default")
      (node (ref "K40") (pin "2") (pinfunction "-_2") (pintype "passive"))
      (node (ref "Q40") (pin "3") (pinfunction "D_3") (pintype "passive"))
    )
    (net (code "214") (name "Net-(K41A-CA)") (class "Default")
      (node (ref "K41") (pin "3") (pinfunction "CA_3") (pintype "passive"))
      (node (ref "X3") (pin "41") (pinfunction "41_41") (pintype "passive"))
    )
    (net (code "215") (name "Net-(K41A-CB)") (class "Default")
      (node (ref "K41") (pin "4") (pinfunction "CB_4") (pintype "passive"))
      (node (ref "X2") (pin "41") (pinfunction "41_41") (pintype "passive"))
    )
    (net (code "216") (name "Net-(K41B--)") (class "Default")
      (node (ref "K41") (pin "2") (pinfunction "-_2") (pintype "passive"))
      (node (ref "Q41") (pin "3") (pinfunction "D_3") (pintype "passive"))
    )
    (net (code "217") (name "Net-(K42A-CA)") (class "Default")
      (node (ref "K42") (pin "3") (pinfunction "CA_3") (pintype "passive"))
      (node (ref "X3") (pin "42") (pinfunction "42_42") (pintype "passive"))
    )
    (net (code "218") (name "Net-(K42A-CB)") (class "Default")
      (node (ref "K42") (pin "4") (pinfunction "CB_4") (pintype "passive"))
      (node (ref "X2") (pin "42") (pinfunction "42_42") (pintype "passive"))
    )
    (net (code "219") (name "Net-(K42B--)") (class "Default")
      (node (ref "K42") (pin "2") (pinfunction "-_2") (pintype "passive"))
      (node (ref "Q42") (pin "3") (pinfunction "D_3") (pintype "passive"))
    )
    (net (code "220") (name "Net-(K43A-CA)") (class "Default")
      (node (ref "K43") (pin "3") (pinfunction "CA_3") (pintype "passive"))
      (node (ref "X3") (pin "43") (pinfunction "43_43") (pintype "passive"))
    )
    (net (code "221") (name "Net-(K43A-CB)") (class "Default")
      (node (ref "K43") (pin "4") (pinfunction "CB_4") (pintype "passive"))
      (node (ref "X2") (pin "43") (pinfunction "43_43") (pintype "passive"))
    )
    (net (code "222") (name "Net-(K43B--)") (class "Default")
      (node (ref "K43") (pin "2") (pinfunction "-_2") (pintype "passive"))
      (node (ref "Q43") (pin "3") (pinfunction "D_3") (pintype "passive"))
    )
    (net (code "223") (name "Net-(K44A-CA)") (class "Default")
      (node (ref "K44") (pin "3") (pinfunction "CA_3") (pintype "passive"))
      (node (ref "X3") (pin "44") (pinfunction "44_44") (pintype "passive"))
    )
    (net (code "224") (name "Net-(K44A-CB)") (class "Default")
      (node (ref "K44") (pin "4") (pinfunction "CB_4") (pintype "passive"))
      (node (ref "X2") (pin "44") (pinfunction "44_44") (pintype "passive"))
    )
    (net (code "225") (name "Net-(K44B--)") (class "Default")
      (node (ref "K44") (pin "2") (pinfunction "-_2") (pintype "passive"))
      (node (ref "Q44") (pin "3") (pinfunction "D_3") (pintype "passive"))
    )
    (net (code "226") (name "Net-(K45A-CA)") (class "Default")
      (node (ref "K45") (pin "3") (pinfunction "CA_3") (pintype "passive"))
      (node (ref "X3") (pin "45") (pinfunction "45_45") (pintype "passive"))
    )
    (net (code "227") (name "Net-(K45A-CB)") (class "Default")
      (node (ref "K45") (pin "4") (pinfunction "CB_4") (pintype "passive"))
      (node (ref "X2") (pin "45") (pinfunction "45_45") (pintype "passive"))
    )
    (net (code "228") (name "Net-(K45B--)") (class "Default")
      (node (ref "K45") (pin "2") (pinfunction "-_2") (pintype "passive"))
      (node (ref "Q45") (pin "3") (pinfunction "D_3") (pintype "passive"))
    )
    (net (code "229") (name "Net-(K46A-CA)") (class "Default")
      (node (ref "K46") (pin "3") (pinfunction "CA_3") (pintype "passive"))
      (node (ref "X3") (pin "46") (pinfunction "46_46") (pintype "passive"))
    )
    (net (code "230") (name "Net-(K46A-CB)") (class "Default")
      (node (ref "K46") (pin "4") (pinfunction "CB_4") (pintype "passive"))
      (node (ref "X2") (pin "46") (pinfunction "46_46") (pintype "passive"))
    )
    (net (code "231") (name "Net-(K46B--)") (class "Default")
      (node (ref "K46") (pin "2") (pinfunction "-_2") (pintype "passive"))
      (node (ref "Q46") (pin "3") (pinfunction "D_3") (pintype "passive"))
    )
    (net (code "232") (name "Net-(K47A-CA)") (class "Default")
      (node (ref "K47") (pin "3") (pinfunction "CA_3") (pintype "passive"))
      (node (ref "X3") (pin "47") (pinfunction "47_47") (pintype "passive"))
    )
    (net (code "233") (name "Net-(K47A-CB)") (class "Default")
      (node (ref "K47") (pin "4") (pinfunction "CB_4") (pintype "passive"))
      (node (ref "X2") (pin "47") (pinfunction "47_47") (pintype "passive"))
    )
    (net (code "234") (name "Net-(K47B--)") (class "Default")
      (node (ref "K47") (pin "2") (pinfunction "-_2") (pintype "passive"))
      (node (ref "Q47") (pin "3") (pinfunction "D_3") (pintype "passive"))
    )
    (net (code "235") (name "Net-(K48A-CA)") (class "Default")
      (node (ref "K48") (pin "3") (pinfunction "CA_3") (pintype "passive"))
      (node (ref "X3") (pin "48") (pinfunction "48_48") (pintype "passive"))
    )
    (net (code "236") (name "Net-(K48A-CB)") (class "Default")
      (node (ref "K48") (pin "4") (pinfunction "CB_4") (pintype "passive"))
      (node (ref "X2") (pin "48") (pinfunction "48_48") (pintype "passive"))
    )
    (net (code "237") (name "Net-(K48B--)") (class "Default")
      (node (ref "K48") (pin "2") (pinfunction "-_2") (pintype "passive"))
      (node (ref "Q48") (pin "3") (pinfunction "D_3") (pintype "passive"))
    )
    (net (code "238") (name "Net-(K49A-CA)") (class "Default")
      (node (ref "K49") (pin "3") (pinfunction "CA_3") (pintype "passive"))
      (node (ref "X3") (pin "49") (pinfunction "49_49") (pintype "passive"))
    )
    (net (code "239") (name "Net-(K49A-CB)") (class "Default")
      (node (ref "K49") (pin "4") (pinfunction "CB_4") (pintype "passive"))
      (node (ref "X2") (pin "49") (pinfunction "49_49") (pintype "passive"))
    )
    (net (code "240") (name "Net-(K49B--)") (class "Default")
      (node (ref "K49") (pin "2") (pinfunction "-_2") (pintype "passive"))
      (node (ref "Q49") (pin "3") (pinfunction "D_3") (pintype "passive"))
    )
    (net (code "241") (name "Net-(K50A-CA)") (class "Default")
      (node (ref "K50") (pin "3") (pinfunction "CA_3") (pintype "passive"))
      (node (ref "X3") (pin "50") (pinfunction "50_50") (pintype "passive"))
    )
    (net (code "242") (name "Net-(K50A-CB)") (class "Default")
      (node (ref "K50") (pin "4") (pinfunction "CB_4") (pintype "passive"))
      (node (ref "X2") (pin "50") (pinfunction "50_50") (pintype "passive"))
    )
    (net (code "243") (name "Net-(K50B--)") (class "Default")
      (node (ref "K50") (pin "2") (pinfunction "-_2") (pintype "passive"))
      (node (ref "Q50") (pin "3") (pinfunction "D_3") (pintype "passive"))
    )
    (net (code "244") (name "Net-(K51A-CA)") (class "Default")
      (node (ref "K51") (pin "3") (pinfunction "CA_3") (pintype "passive"))
      (node (ref "X3") (pin "51") (pinfunction "51_51") (pintype "passive"))
    )
    (net (code "245") (name "Net-(K51A-CB)") (class "Default")
      (node (ref "K51") (pin "4") (pinfunction "CB_4") (pintype "passive"))
      (node (ref "X2") (pin "51") (pinfunction "51_51") (pintype "passive"))
    )
    (net (code "246") (name "Net-(K51B--)") (class "Default")
      (node (ref "K51") (pin "2") (pinfunction "-_2") (pintype "passive"))
      (node (ref "Q51") (pin "3") (pinfunction "D_3") (pintype "passive"))
    )
    (net (code "247") (name "Net-(K52A-CA)") (class "Default")
      (node (ref "K52") (pin "3") (pinfunction "CA_3") (pintype "passive"))
      (node (ref "X3") (pin "52") (pinfunction "52_52") (pintype "passive"))
    )
    (net (code "248") (name "Net-(K52A-CB)") (class "Default")
      (node (ref "K52") (pin "4") (pinfunction "CB_4") (pintype "passive"))
      (node (ref "X2") (pin "52") (pinfunction "52_52") (pintype "passive"))
    )
    (net (code "249") (name "Net-(K52B--)") (class "Default")
      (node (ref "K52") (pin "2") (pinfunction "-_2") (pintype "passive"))
      (node (ref "Q52") (pin "3") (pinfunction "D_3") (pintype "passive"))
    )
    (net (code "250") (name "Net-(K53A-CA)") (class "Default")
      (node (ref "K53") (pin "3") (pinfunction "CA_3") (pintype "passive"))
      (node (ref "X3") (pin "53") (pinfunction "53_53") (pintype "passive"))
    )
    (net (code "251") (name "Net-(K53A-CB)") (class "Default")
      (node (ref "K53") (pin "4") (pinfunction "CB_4") (pintype "passive"))
      (node (ref "X2") (pin "53") (pinfunction "53_53") (pintype "passive"))
    )
    (net (code "252") (name "Net-(K53B--)") (class "Default")
      (node (ref "K53") (pin "2") (pinfunction "-_2") (pintype "passive"))
      (node (ref "Q53") (pin "3") (pinfunction "D_3") (pintype "passive"))
    )
    (net (code "253") (name "Net-(K54A-CA)") (class "Default")
      (node (ref "K54") (pin "3") (pinfunction "CA_3") (pintype "passive"))
      (node (ref "X3") (pin "54") (pinfunction "54_54") (pintype "passive"))
    )
    (net (code "254") (name "Net-(K54A-CB)") (class "Default")
      (node (ref "K54") (pin "4") (pinfunction "CB_4") (pintype "passive"))
      (node (ref "X2") (pin "54") (pinfunction "54_54") (pintype "passive"))
    )
    (net (code "255") (name "Net-(K54B--)") (class "Default")
      (node (ref "K54") (pin "2") (pinfunction "-_2") (pintype "passive"))
      (node (ref "Q54") (pin "3") (pinfunction "D_3") (pintype "passive"))
    )
    (net (code "256") (name "Net-(K55A-CA)") (class "Default")
      (node (ref "K55") (pin "3") (pinfunction "CA_3") (pintype "passive"))
      (node (ref "X3") (pin "55") (pinfunction "55_55") (pintype "passive"))
    )
    (net (code "257") (name "Net-(K55A-CB)") (class "Default")
      (node (ref "K55") (pin "4") (pinfunction "CB_4") (pintype "passive"))
      (node (ref "X2") (pin "55") (pinfunction "55_55") (pintype "passive"))
    )
    (net (code "258") (name "Net-(K55B--)") (class "Default")
      (node (ref "K55") (pin "2") (pinfunction "-_2") (pintype "passive"))
      (node (ref "Q55") (pin "3") (pinfunction "D_3") (pintype "passive"))
    )
    (net (code "259") (name "Net-(K56A-CA)") (class "Default")
      (node (ref "K56") (pin "3") (pinfunction "CA_3") (pintype "passive"))
      (node (ref "X3") (pin "56") (pinfunction "56_56") (pintype "passive"))
    )
    (net (code "260") (name "Net-(K56A-CB)") (class "Default")
      (node (ref "K56") (pin "4") (pinfunction "CB_4") (pintype "passive"))
      (node (ref "X2") (pin "56") (pinfunction "56_56") (pintype "passive"))
    )
    (net (code "261") (name "Net-(K56B--)") (class "Default")
      (node (ref "K56") (pin "2") (pinfunction "-_2") (pintype "passive"))
      (node (ref "Q56") (pin "3") (pinfunction "D_3") (pintype "passive"))
    )
    (net (code "262") (name "Net-(K57A-CA)") (class "Default")
      (node (ref "K57") (pin "3") (pinfunction "CA_3") (pintype "passive"))
      (node (ref "X3") (pin "57") (pinfunction "57_57") (pintype "passive"))
    )
    (net (code "263") (name "Net-(K57A-CB)") (class "Default")
      (node (ref "K57") (pin "4") (pinfunction "CB_4") (pintype "passive"))
      (node (ref "X2") (pin "57") (pinfunction "57_57") (pintype "passive"))
    )
    (net (code "264") (name "Net-(K57B--)") (class "Default")
      (node (ref "K57") (pin "2") (pinfunction "-_2") (pintype "passive"))
      (node (ref "Q57") (pin "3") (pinfunction "D_3") (pintype "passive"))
    )
    (net (code "265") (name "Net-(K58A-CA)") (class "Default")
      (node (ref "K58") (pin "3") (pinfunction "CA_3") (pintype "passive"))
      (node (ref "X3") (pin "58") (pinfunction "58_58") (pintype "passive"))
    )
    (net (code "266") (name "Net-(K58A-CB)") (class "Default")
      (node (ref "K58") (pin "4") (pinfunction "CB_4") (pintype "passive"))
      (node (ref "X2") (pin "58") (pinfunction "58_58") (pintype "passive"))
    )
    (net (code "267") (name "Net-(K58B--)") (class "Default")
      (node (ref "K58") (pin "2") (pinfunction "-_2") (pintype "passive"))
      (node (ref "Q58") (pin "3") (pinfunction "D_3") (pintype "passive"))
    )
    (net (code "268") (name "Net-(K59A-CA)") (class "Default")
      (node (ref "K59") (pin "3") (pinfunction "CA_3") (pintype "passive"))
      (node (ref "X3") (pin "59") (pinfunction "59_59") (pintype "passive"))
    )
    (net (code "269") (name "Net-(K59A-CB)") (class "Default")
      (node (ref "K59") (pin "4") (pinfunction "CB_4") (pintype "passive"))
      (node (ref "X2") (pin "59") (pinfunction "59_59") (pintype "passive"))
    )
    (net (code "270") (name "Net-(K59B--)") (class "Default")
      (node (ref "K59") (pin "2") (pinfunction "-_2") (pintype "passive"))
      (node (ref "Q59") (pin "3") (pinfunction "D_3") (pintype "passive"))
    )
    (net (code "271") (name "Net-(K60A-CA)") (class "Default")
      (node (ref "K60") (pin "3") (pinfunction "CA_3") (pintype "passive"))
      (node (ref "X3") (pin "60") (pinfunction "60_60") (pintype "passive"))
    )
    (net (code "272") (name "Net-(K60A-CB)") (class "Default")
      (node (ref "K60") (pin "4") (pinfunction "CB_4") (pintype "passive"))
      (node (ref "X2") (pin "60") (pinfunction "60_60") (pintype "passive"))
    )
    (net (code "273") (name "Net-(K60B--)") (class "Default")
      (node (ref "K60") (pin "2") (pinfunction "-_2") (pintype "passive"))
      (node (ref "Q60") (pin "3") (pinfunction "D_3") (pintype "passive"))
    )
    (net (code "274") (name "Net-(K61A-CA)") (class "Default")
      (node (ref "K61") (pin "3") (pinfunction "CA_3") (pintype "passive"))
      (node (ref "X3") (pin "61") (pinfunction "61_61") (pintype "passive"))
    )
    (net (code "275") (name "Net-(K61A-CB)") (class "Default")
      (node (ref "K61") (pin "4") (pinfunction "CB_4") (pintype "passive"))
      (node (ref "X2") (pin "61") (pinfunction "61_61") (pintype "passive"))
    )
    (net (code "276") (name "Net-(K61B--)") (class "Default")
      (node (ref "K61") (pin "2") (pinfunction "-_2") (pintype "passive"))
      (node (ref "Q61") (pin "3") (pinfunction "D_3") (pintype "passive"))
    )
    (net (code "277") (name "Net-(K62A-CA)") (class "Default")
      (node (ref "K62") (pin "3") (pinfunction "CA_3") (pintype "passive"))
      (node (ref "X3") (pin "62") (pinfunction "62_62") (pintype "passive"))
    )
    (net (code "278") (name "Net-(K62A-CB)") (class "Default")
      (node (ref "K62") (pin "4") (pinfunction "CB_4") (pintype "passive"))
      (node (ref "X2") (pin "62") (pinfunction "62_62") (pintype "passive"))
    )
    (net (code "279") (name "Net-(K62B--)") (class "Default")
      (node (ref "K62") (pin "2") (pinfunction "-_2") (pintype "passive"))
      (node (ref "Q62") (pin "3") (pinfunction "D_3") (pintype "passive"))
    )
    (net (code "280") (name "Net-(K63A-CA)") (class "Default")
      (node (ref "K63") (pin "3") (pinfunction "CA_3") (pintype "passive"))
      (node (ref "X3") (pin "63") (pinfunction "63_63") (pintype "passive"))
    )
    (net (code "281") (name "Net-(K63A-CB)") (class "Default")
      (node (ref "K63") (pin "4") (pinfunction "CB_4") (pintype "passive"))
      (node (ref "X2") (pin "63") (pinfunction "63_63") (pintype "passive"))
    )
    (net (code "282") (name "Net-(K63B--)") (class "Default")
      (node (ref "K63") (pin "2") (pinfunction "-_2") (pintype "passive"))
      (node (ref "Q63") (pin "3") (pinfunction "D_3") (pintype "passive"))
    )
    (net (code "283") (name "Net-(K64A-CA)") (class "Default")
      (node (ref "K64") (pin "3") (pinfunction "CA_3") (pintype "passive"))
      (node (ref "X3") (pin "64") (pinfunction "64_64") (pintype "passive"))
    )
    (net (code "284") (name "Net-(K64A-CB)") (class "Default")
      (node (ref "K64") (pin "4") (pinfunction "CB_4") (pintype "passive"))
      (node (ref "X2") (pin "64") (pinfunction "64_64") (pintype "passive"))
    )
    (net (code "285") (name "Net-(K64B--)") (class "Default")
      (node (ref "K64") (pin "2") (pinfunction "-_2") (pintype "passive"))
      (node (ref "Q64") (pin "3") (pinfunction "D_3") (pintype "passive"))
    )
  )
)
